# SmartVehicle_3.net
KiCad netlist of a schematic drawn in EAGLE
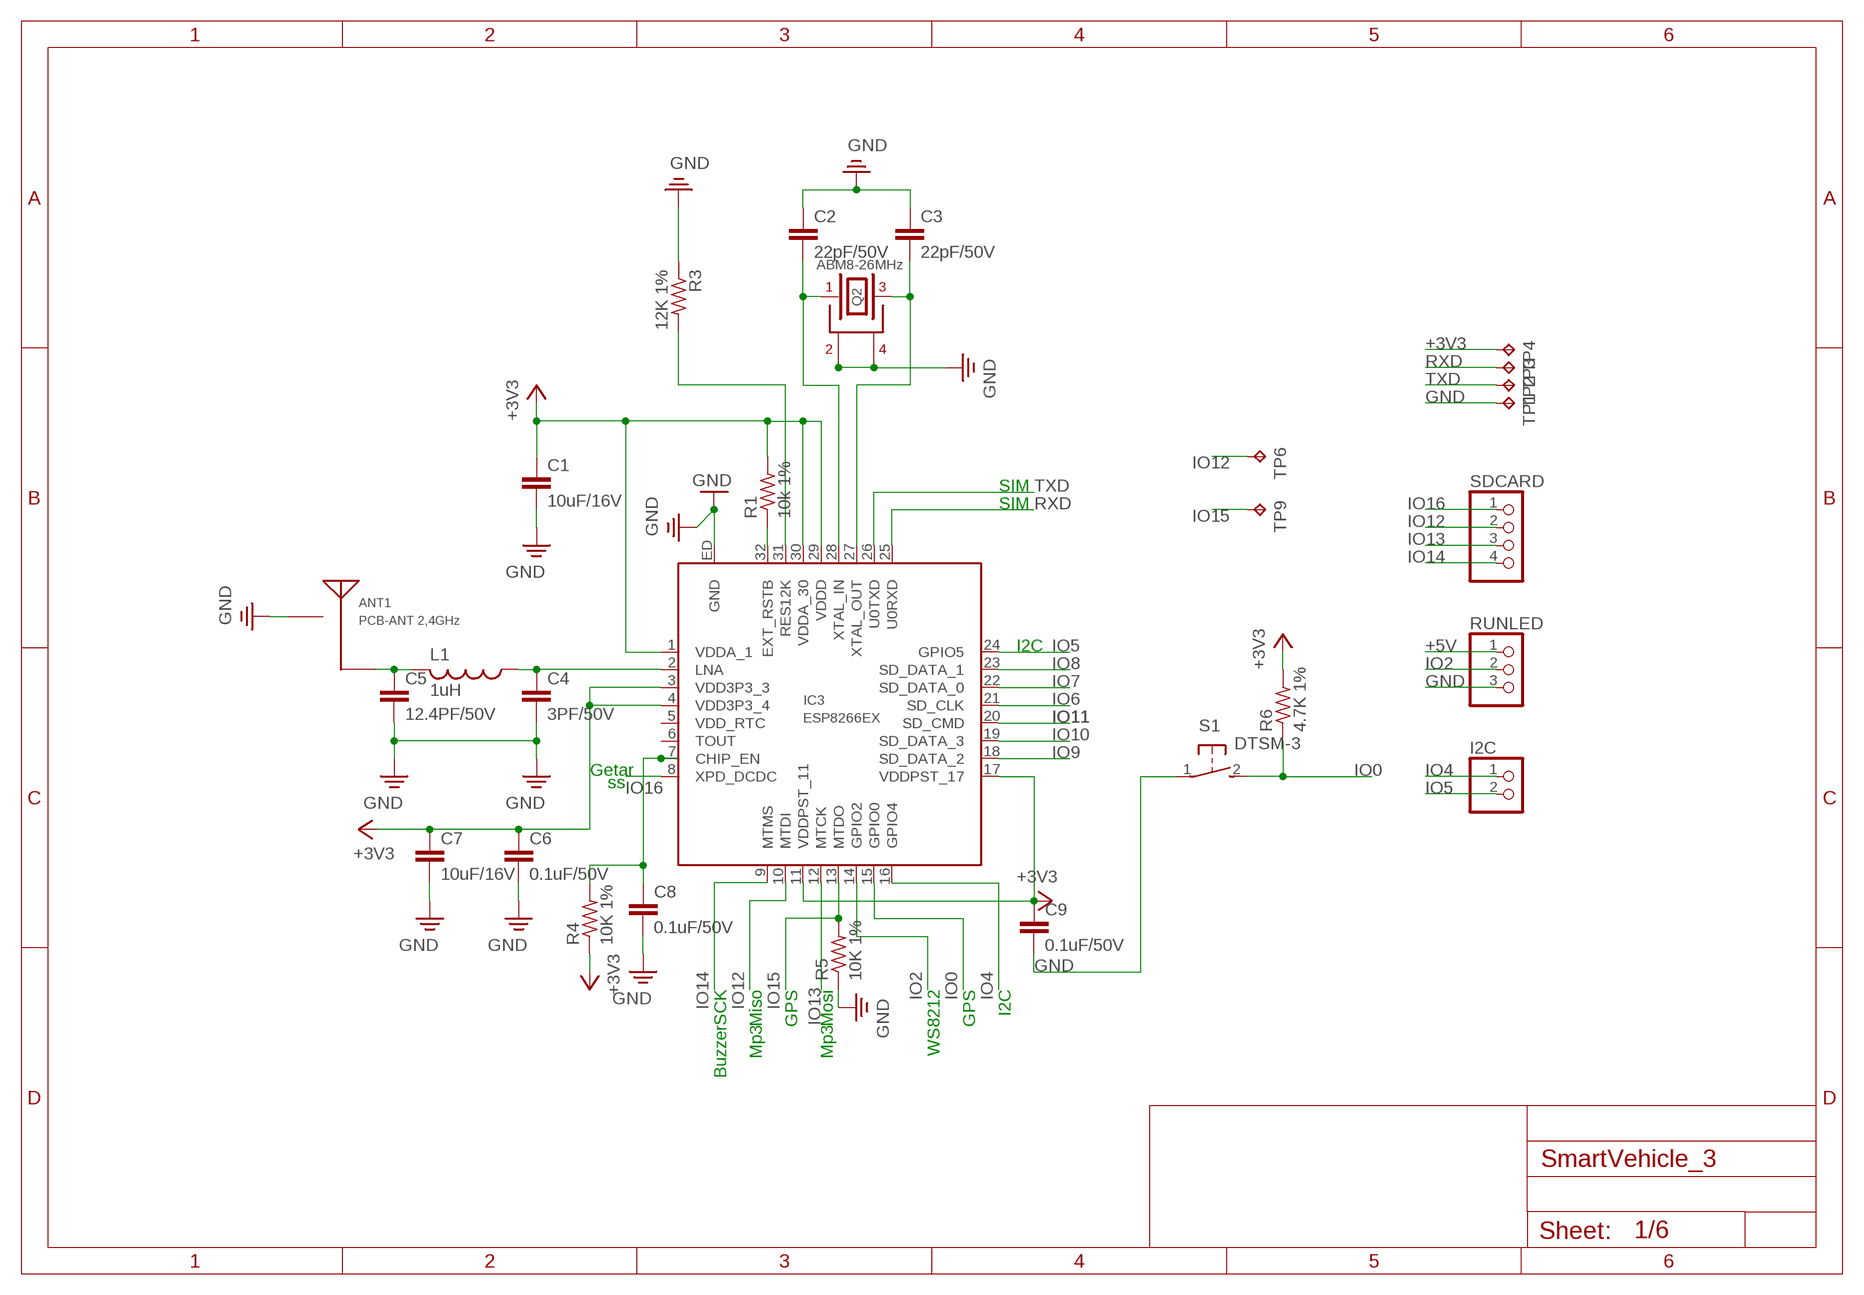
[diagram p0: schematic, sheet 1]
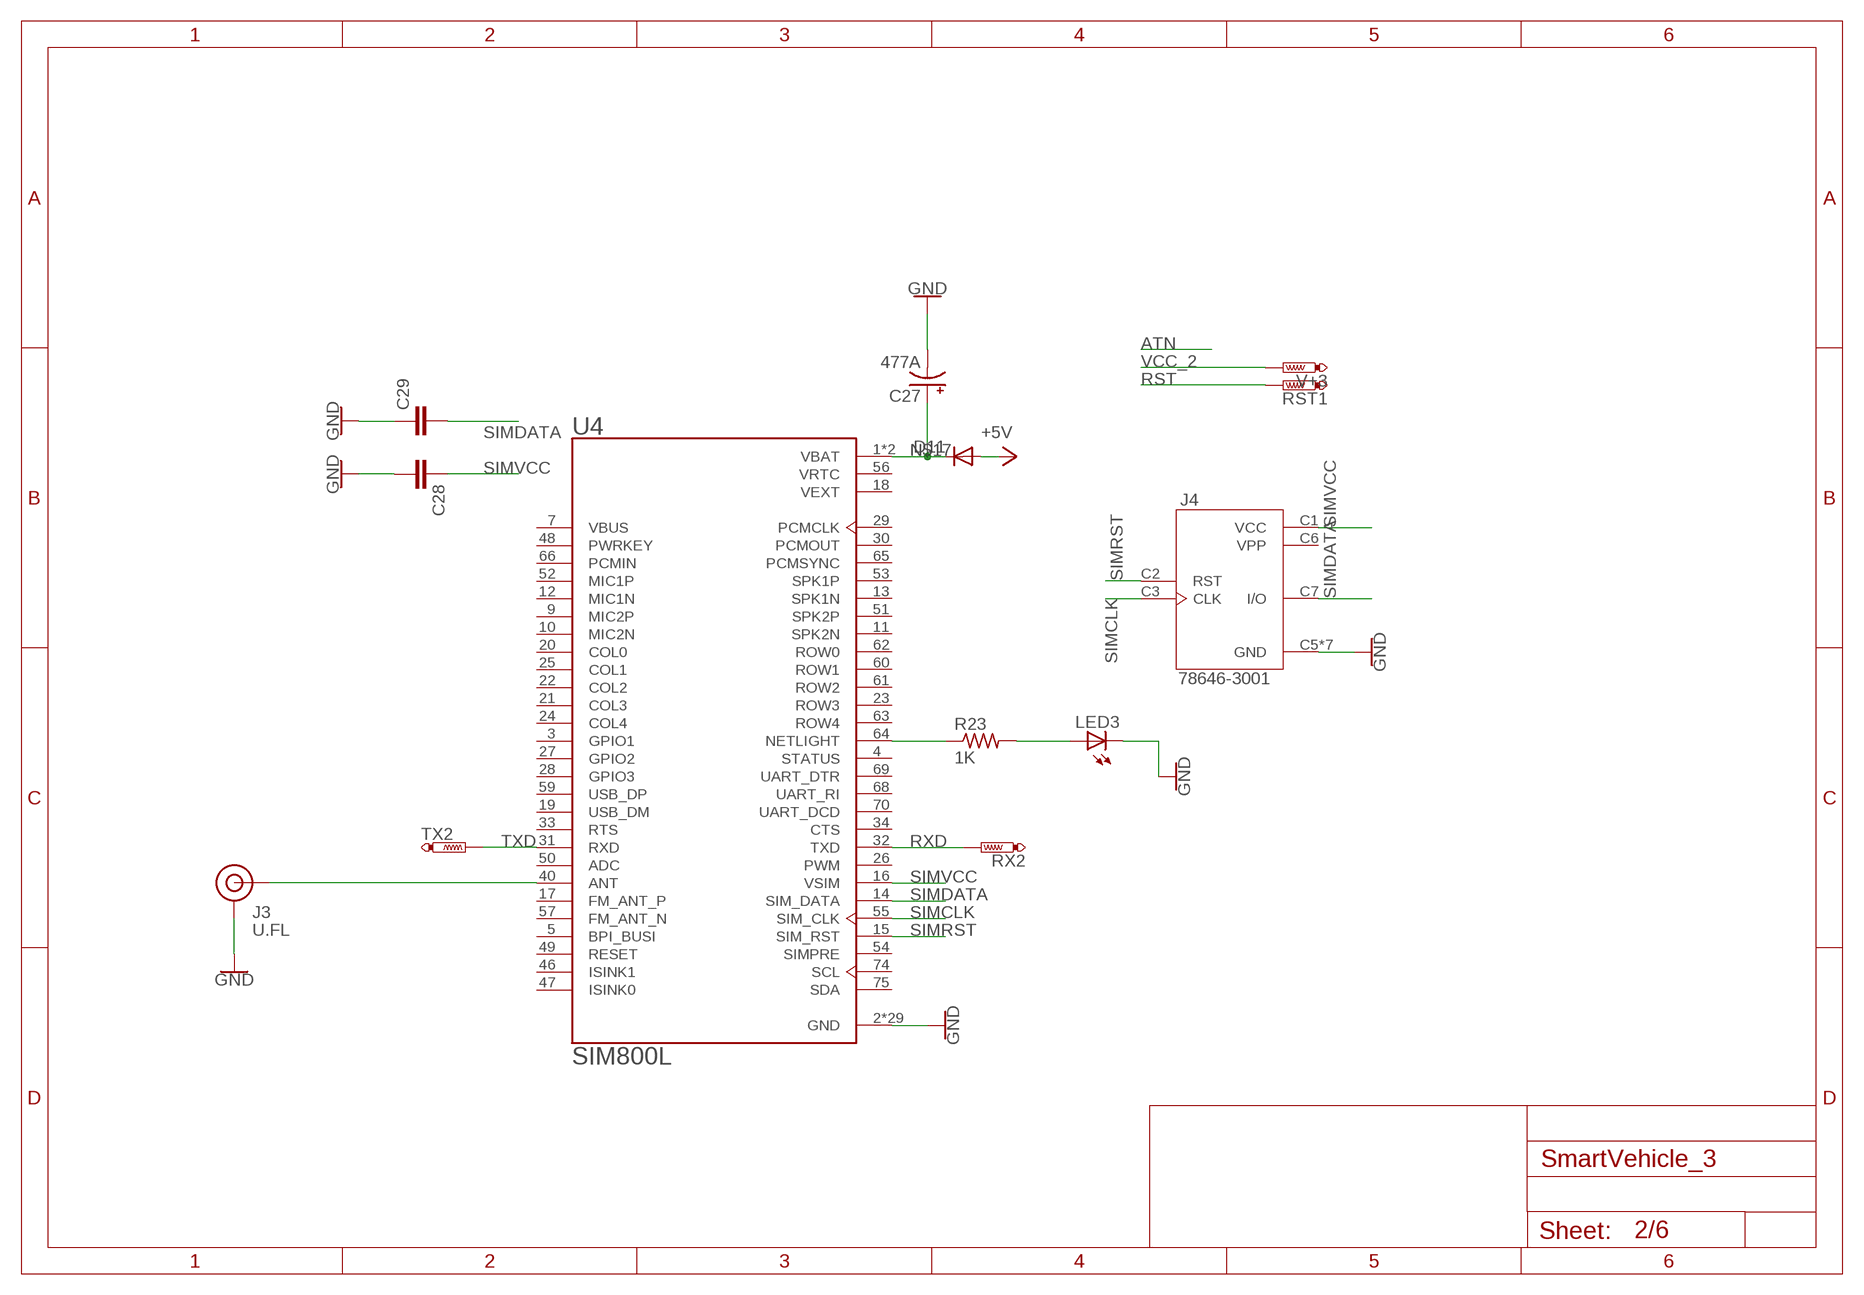
[diagram p1: schematic, sheet 2]
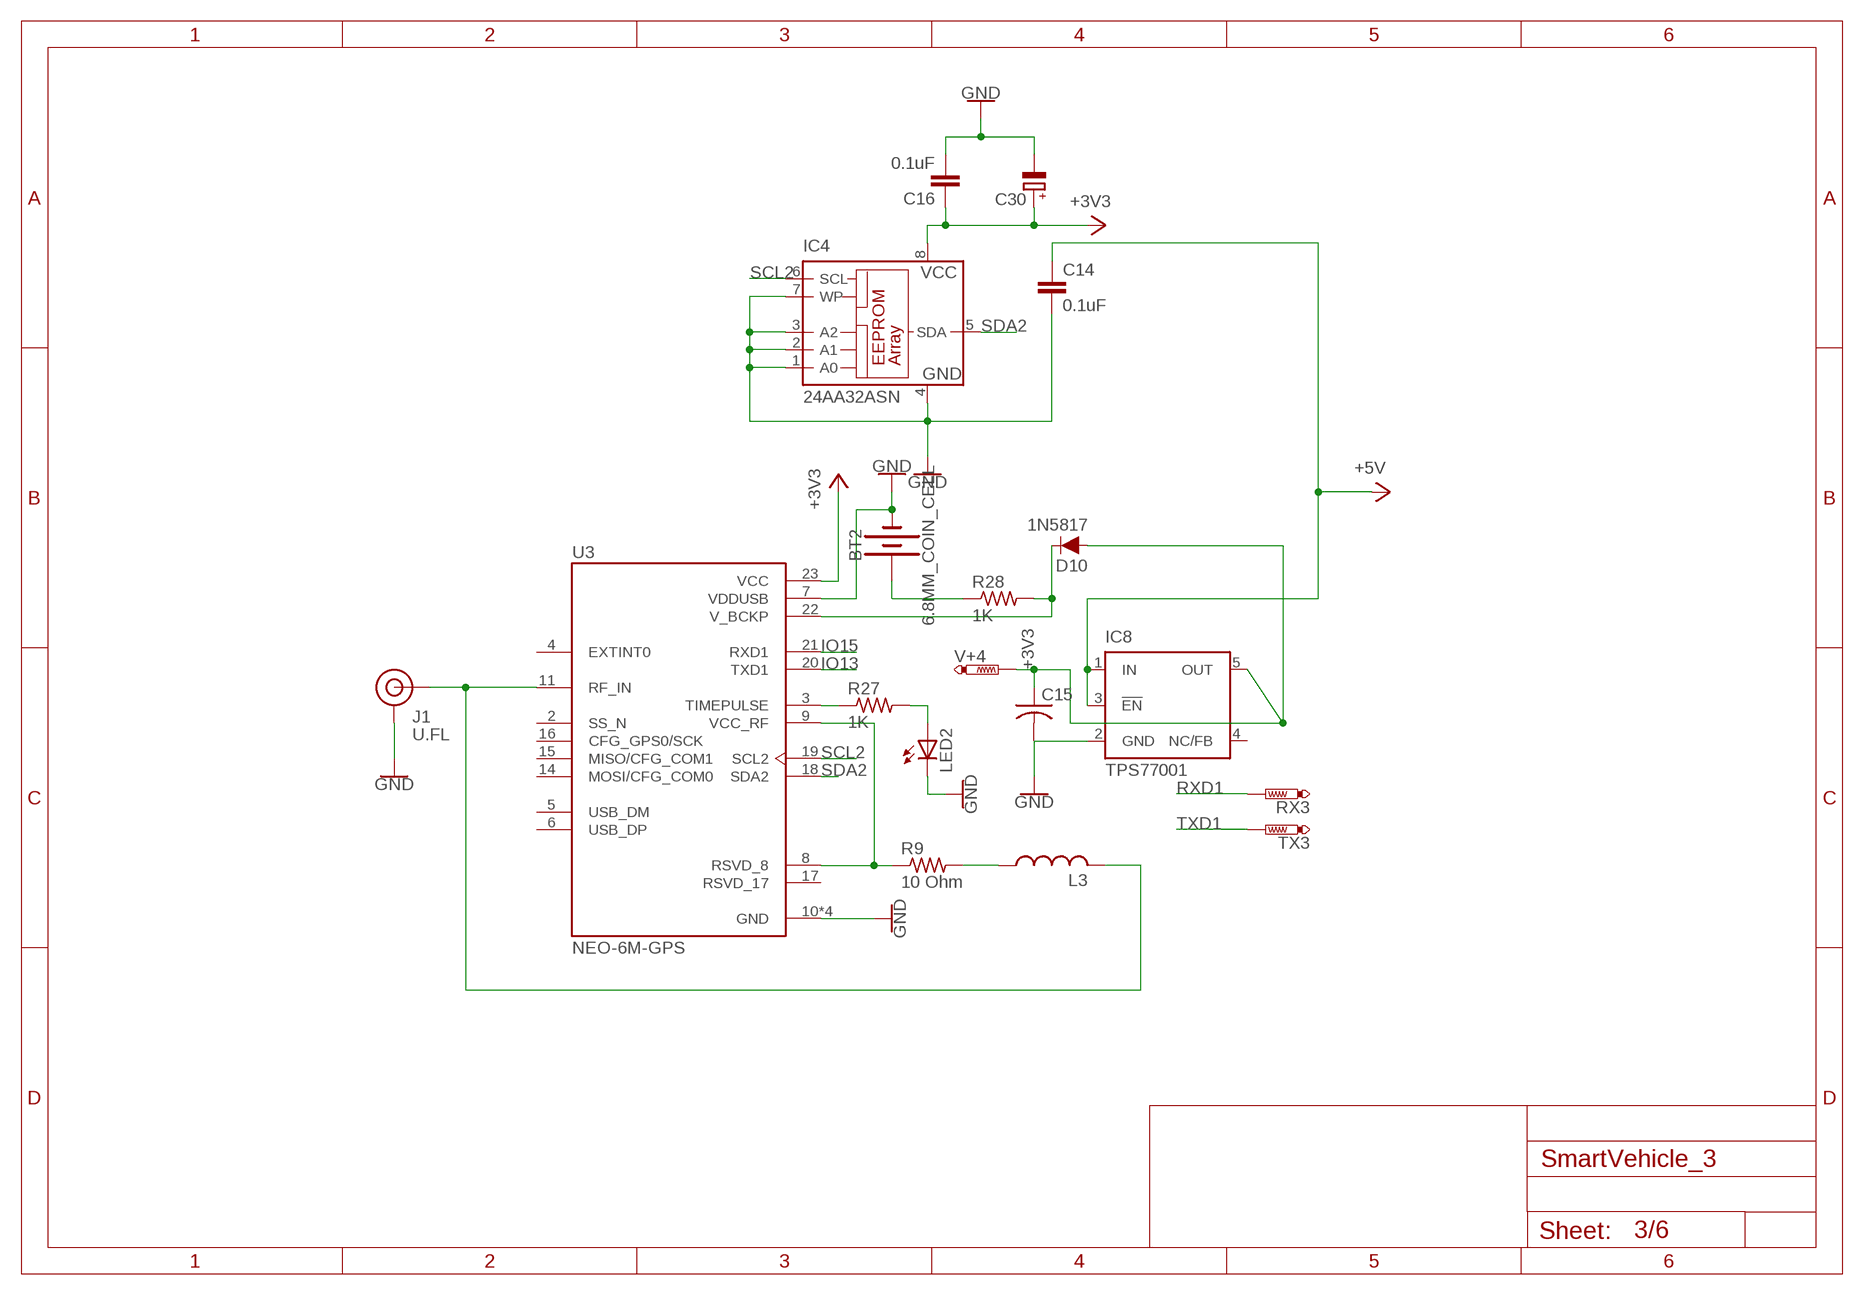
[diagram p2: schematic, sheet 3]
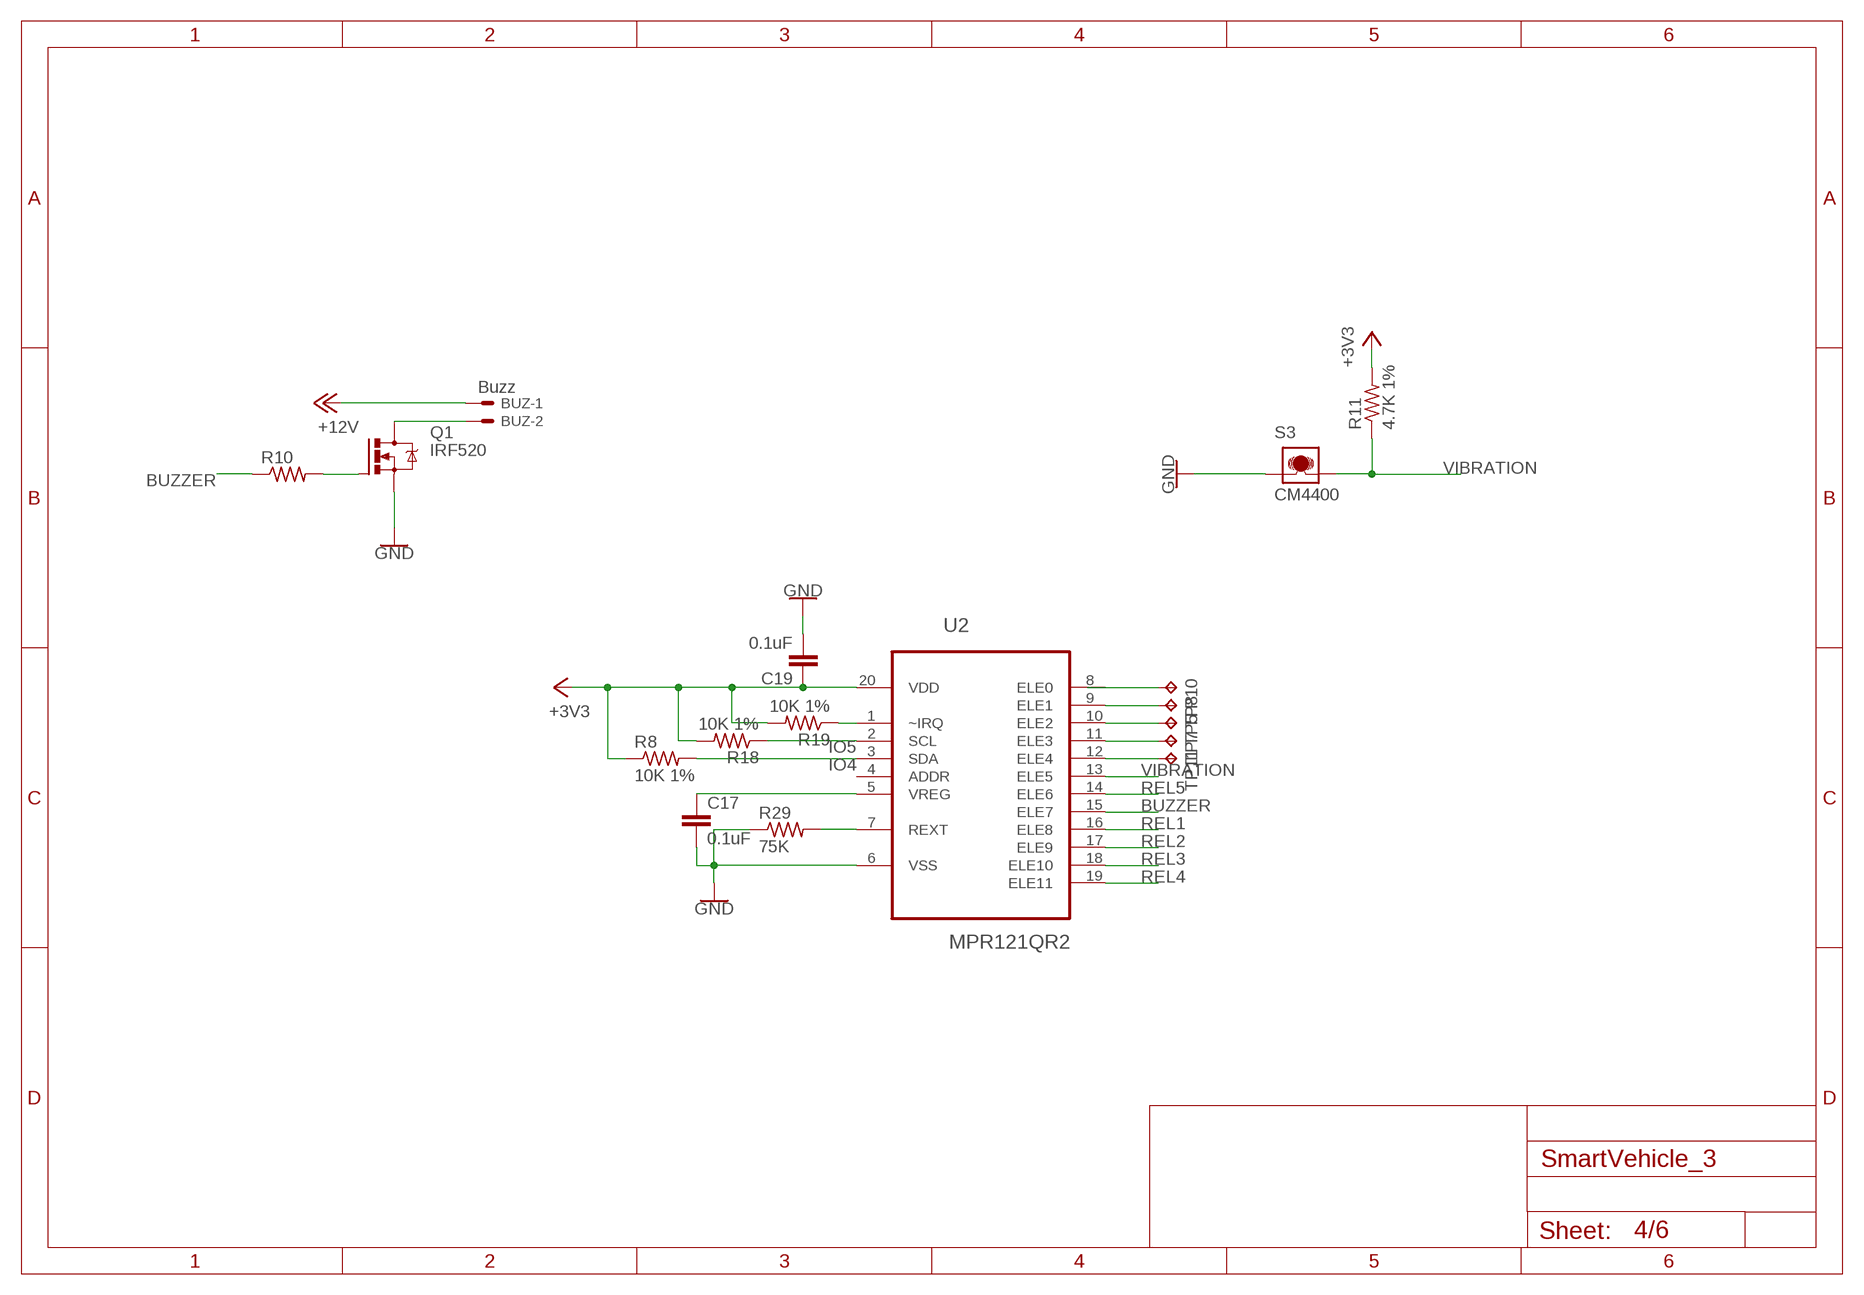
[diagram p3: schematic, sheet 4]
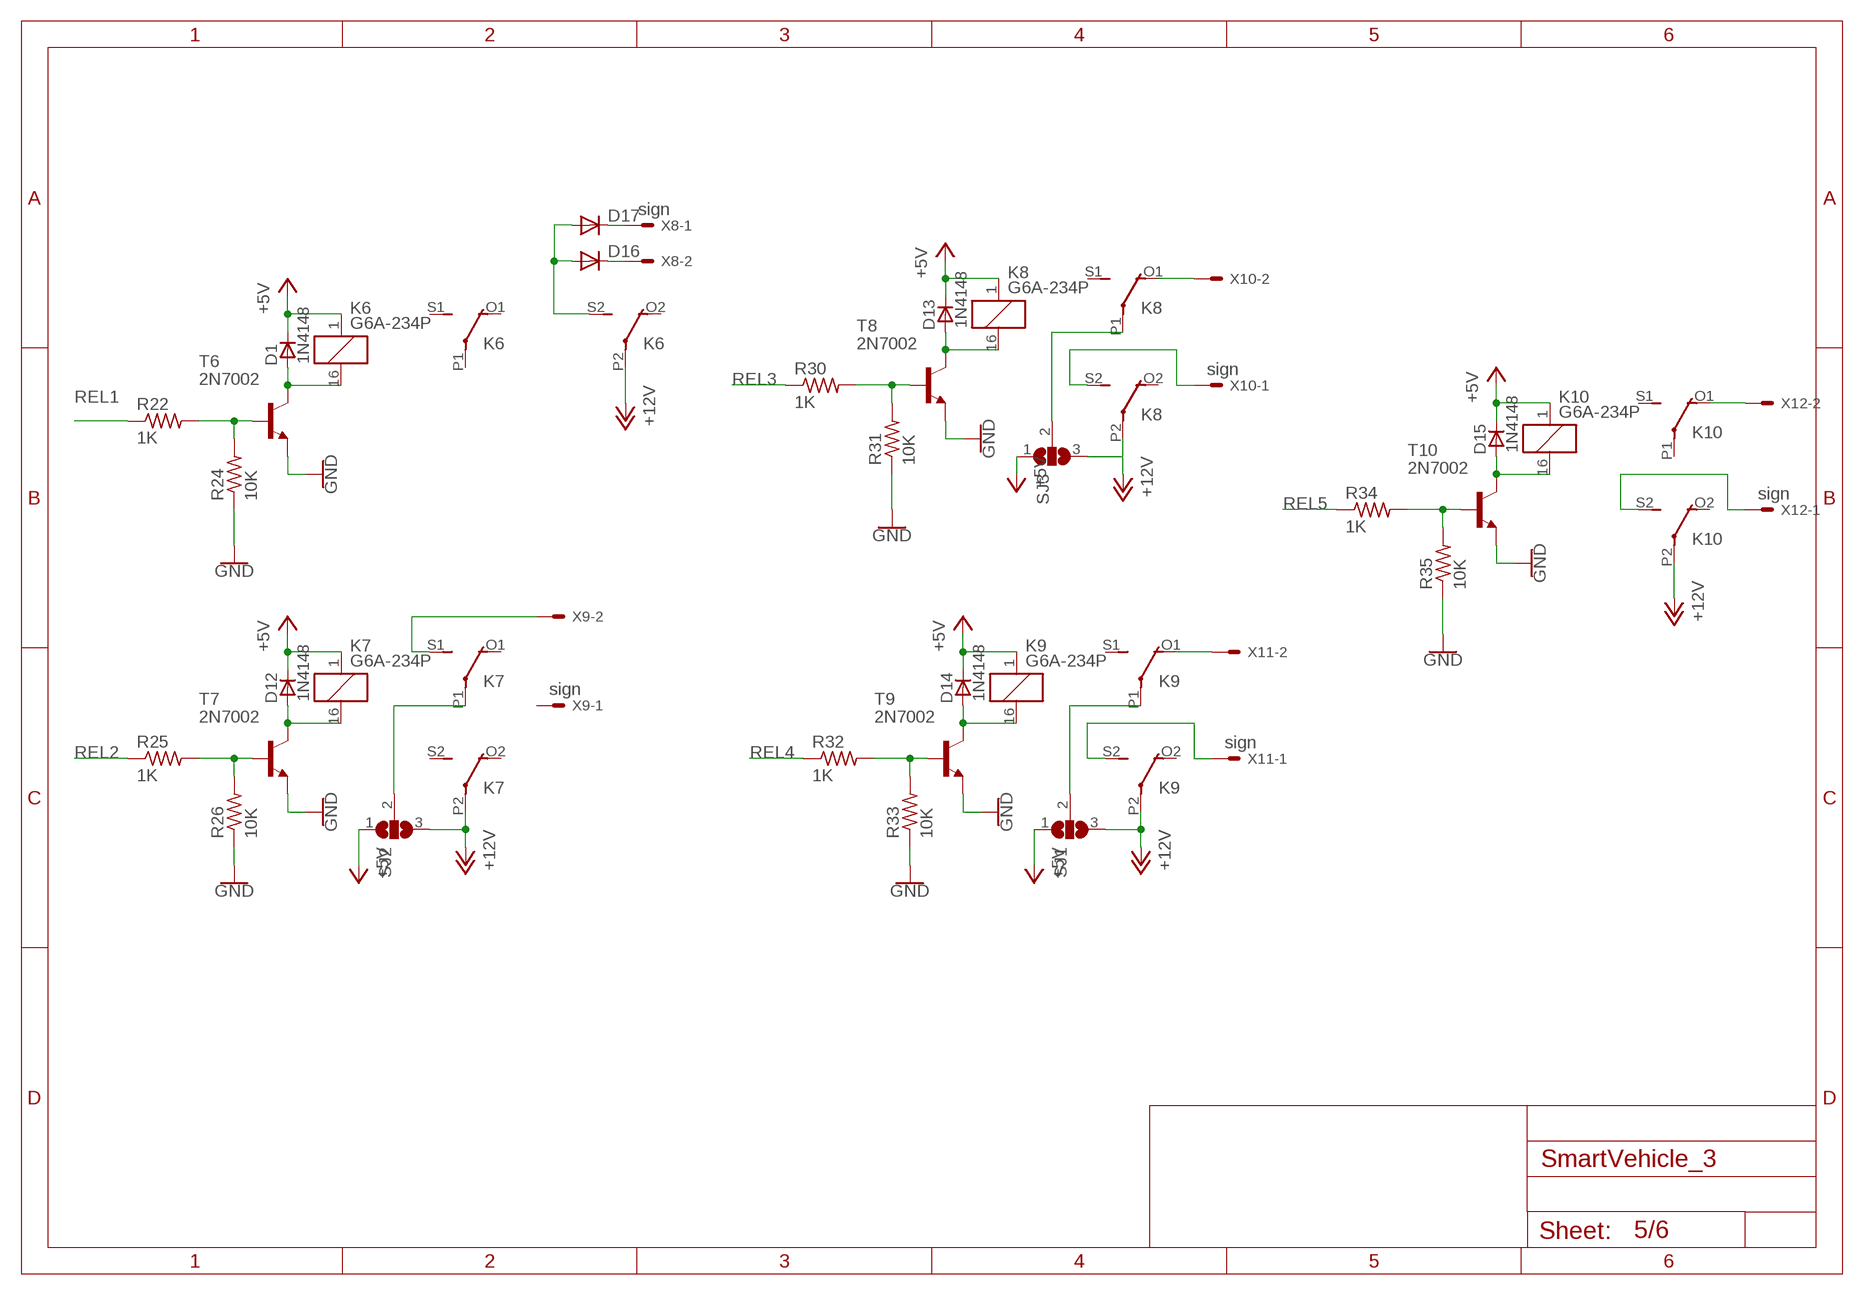
[diagram p4: schematic, sheet 5]
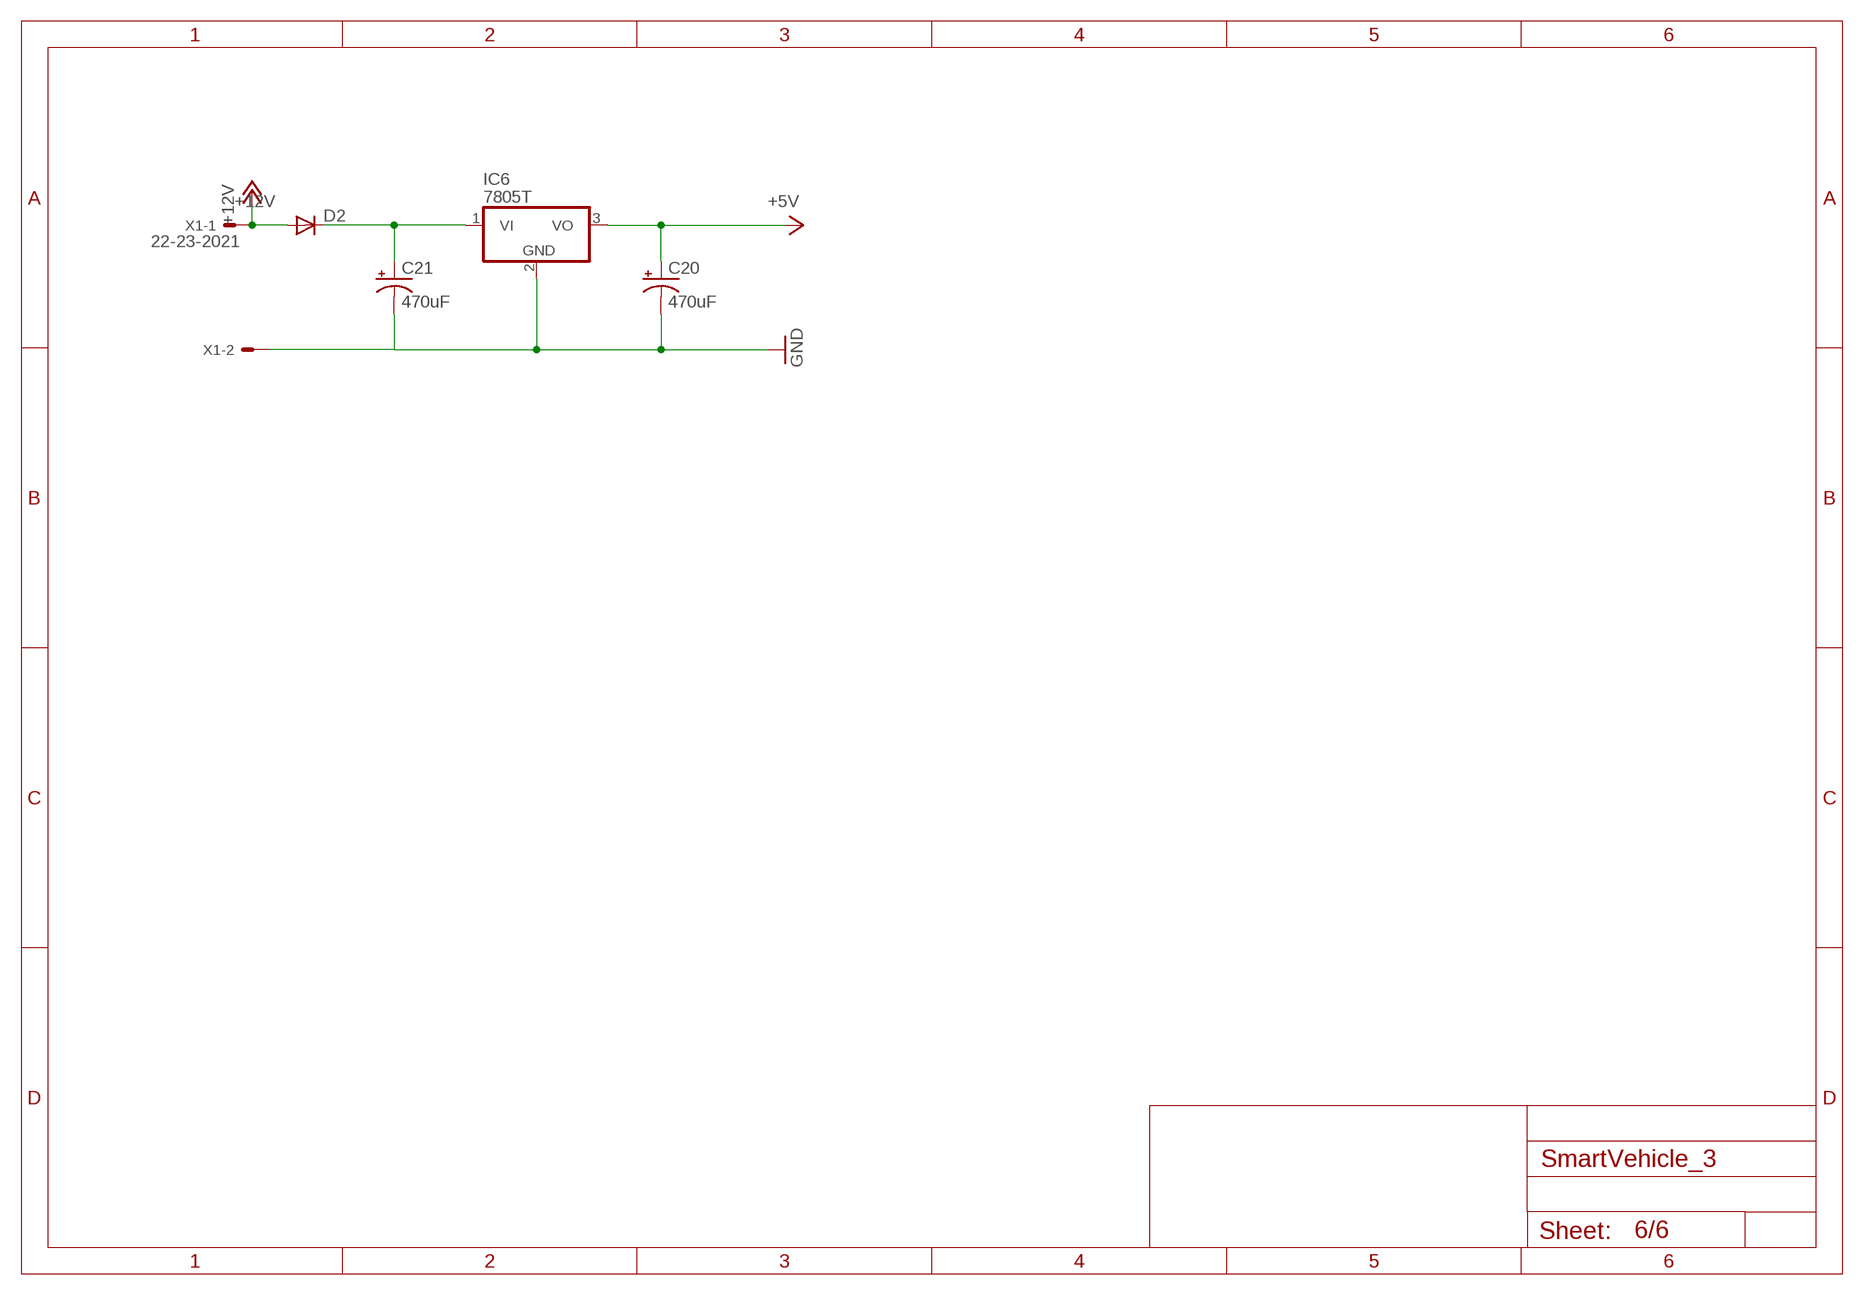
[diagram p5: schematic, sheet 6]

(export (version "E")
  (design (tool "Eeschema 10.0.6"))
  (components
    (comp (ref "BT2")
      (value "6.8MM_COIN_CELL")
      (footprint "eagle-import:BATTCON-6.8MM")
      (libsource (lib "eagle-import") (part "BATTERY-6.8MM_SMD"))
    )
    (comp (ref "C14")
      (value "0.1uF")
      (footprint "eagle-import:0603")
      (libsource (lib "eagle-import") (part "0.1UF-0603-25V-(+80/-20%)"))
    )
    (comp (ref "C15")
      (value "C-USC0603K")
      (footprint "eagle-import:C0603K")
      (libsource (lib "eagle-import") (part "C-USC0603K"))
    )
    (comp (ref "C16")
      (value "0.1uF")
      (footprint "eagle-import:0603")
      (libsource (lib "eagle-import") (part "0.1UF-0603-25V-(+80/-20%)"))
    )
    (comp (ref "C30")
      (value "CPOL-EUCT3528")
      (footprint "eagle-import:CT3528")
      (libsource (lib "eagle-import") (part "CPOL-EUCT3528"))
    )
    (comp (ref "D10")
      (value "1N5817")
      (footprint "eagle-import:SOD-323")
      (libsource (lib "eagle-import") (part "DIODE-BAS16J"))
    )
    (comp (ref "IC4")
      (value "24AA32ASN")
      (footprint "eagle-import:SO-08")
      (fields (field (name "MF") "MICROCHIP") (field (name "MPN") "24AA32A-I/SN"))
      (libsource (lib "eagle-import") (part "24SNAA32A"))
    )
    (comp (ref "IC8")
      (value "TPS77001")
      (footprint "eagle-import:SOT23-DBV")
      (fields (field (name "MF") "TEXAS INSTRUMENTS") (field (name "MPN") "TPS77001DBVT"))
      (libsource (lib "eagle-import") (part "TPS77001"))
    )
    (comp (ref "J1")
      (value "U.FL")
      (footprint "eagle-import:U.FL")
      (libsource (lib "eagle-import") (part "U.FL2PIN"))
    )
    (comp (ref "L3")
      (value "L-USL2012C")
      (footprint "eagle-import:L2012C")
      (libsource (lib "eagle-import") (part "L-USL2012C"))
    )
    (comp (ref "LED2")
      (value "LEDCHIP-LED0805")
      (footprint "eagle-import:CHIP-LED0805")
      (libsource (lib "eagle-import") (part "LEDCHIP-LED0805"))
    )
    (comp (ref "R9")
      (value "10 Ohm")
      (footprint "eagle-import:R0603")
      (libsource (lib "eagle-import") (part "R-US_R0603"))
    )
    (comp (ref "R27")
      (value "1K")
      (footprint "eagle-import:R0603")
      (libsource (lib "eagle-import") (part "R-US_R0603"))
    )
    (comp (ref "R28")
      (value "1K")
      (footprint "eagle-import:R0603")
      (libsource (lib "eagle-import") (part "R-US_R0603"))
    )
    (comp (ref "RX3")
      (value "PTR1TP08R")
      (footprint "eagle-import:TP08R")
      (libsource (lib "eagle-import") (part "PTR1TP08R"))
    )
    (comp (ref "TX3")
      (value "PTR1TP08R")
      (footprint "eagle-import:TP08R")
      (libsource (lib "eagle-import") (part "PTR1TP08R"))
    )
    (comp (ref "U3")
      (value "NEO-6M-GPS")
      (footprint "eagle-import:XCVR_NEO-6M-GPS")
      (fields (field (name "MF") "u-blox"))
      (libsource (lib "eagle-import") (part "NEO-6M-GPS"))
    )
    (comp (ref "V+4")
      (value "PTR1TP08R")
      (footprint "eagle-import:TP08R")
      (libsource (lib "eagle-import") (part "PTR1TP08R"))
    )
    (comp (ref "D1")
      (value "1N4148")
      (footprint "eagle-import:SOD80_DO213AA_MINIMELF")
      (libsource (lib "eagle-import") (part "LL4148"))
    )
    (comp (ref "D12")
      (value "1N4148")
      (footprint "eagle-import:SOD80_DO213AA_MINIMELF")
      (libsource (lib "eagle-import") (part "LL4148"))
    )
    (comp (ref "D13")
      (value "1N4148")
      (footprint "eagle-import:SOD80_DO213AA_MINIMELF")
      (libsource (lib "eagle-import") (part "LL4148"))
    )
    (comp (ref "D14")
      (value "1N4148")
      (footprint "eagle-import:SOD80_DO213AA_MINIMELF")
      (libsource (lib "eagle-import") (part "LL4148"))
    )
    (comp (ref "D15")
      (value "1N4148")
      (footprint "eagle-import:SOD80_DO213AA_MINIMELF")
      (libsource (lib "eagle-import") (part "LL4148"))
    )
    (comp (ref "D16")
      (value "DIODE-DO214AA")
      (footprint "eagle-import:DO214AA")
      (libsource (lib "eagle-import") (part "DIODE-DO214AA"))
    )
    (comp (ref "D17")
      (value "DIODE-DO214AA")
      (footprint "eagle-import:DO214AA")
      (libsource (lib "eagle-import") (part "DIODE-DO214AA"))
    )
    (comp (ref "K6")
      (value "G6A-234P")
      (footprint "eagle-import:G6A-234P")
      (libsource (lib "eagle-import") (part "G6A-234P"))
    )
    (comp (ref "K7")
      (value "G6A-234P")
      (footprint "eagle-import:G6A-234P")
      (libsource (lib "eagle-import") (part "G6A-234P"))
    )
    (comp (ref "K8")
      (value "G6A-234P")
      (footprint "eagle-import:G6A-234P")
      (libsource (lib "eagle-import") (part "G6A-234P"))
    )
    (comp (ref "K9")
      (value "G6A-234P")
      (footprint "eagle-import:G6A-234P")
      (libsource (lib "eagle-import") (part "G6A-234P"))
    )
    (comp (ref "K10")
      (value "G6A-234P")
      (footprint "eagle-import:G6A-234P")
      (libsource (lib "eagle-import") (part "G6A-234P"))
    )
    (comp (ref "R22")
      (value "1K")
      (footprint "eagle-import:M0805")
      (libsource (lib "eagle-import") (part "resistor_R-US_M0805"))
    )
    (comp (ref "R24")
      (value "10K")
      (footprint "eagle-import:M0805")
      (libsource (lib "eagle-import") (part "resistor_R-US_M0805"))
    )
    (comp (ref "R25")
      (value "1K")
      (footprint "eagle-import:M0805")
      (libsource (lib "eagle-import") (part "resistor_R-US_M0805"))
    )
    (comp (ref "R26")
      (value "10K")
      (footprint "eagle-import:M0805")
      (libsource (lib "eagle-import") (part "resistor_R-US_M0805"))
    )
    (comp (ref "R30")
      (value "1K")
      (footprint "eagle-import:M0805")
      (libsource (lib "eagle-import") (part "resistor_R-US_M0805"))
    )
    (comp (ref "R31")
      (value "10K")
      (footprint "eagle-import:M0805")
      (libsource (lib "eagle-import") (part "resistor_R-US_M0805"))
    )
    (comp (ref "R32")
      (value "1K")
      (footprint "eagle-import:M0805")
      (libsource (lib "eagle-import") (part "resistor_R-US_M0805"))
    )
    (comp (ref "R33")
      (value "10K")
      (footprint "eagle-import:M0805")
      (libsource (lib "eagle-import") (part "resistor_R-US_M0805"))
    )
    (comp (ref "R34")
      (value "1K")
      (footprint "eagle-import:M0805")
      (libsource (lib "eagle-import") (part "resistor_R-US_M0805"))
    )
    (comp (ref "R35")
      (value "10K")
      (footprint "eagle-import:M0805")
      (libsource (lib "eagle-import") (part "resistor_R-US_M0805"))
    )
    (comp (ref "SJ1")
      (value "SJ2W")
      (footprint "eagle-import:SJ_2")
      (libsource (lib "eagle-import") (part "SJ2W"))
    )
    (comp (ref "SJ2")
      (value "SJ2W")
      (footprint "eagle-import:SJ_2")
      (libsource (lib "eagle-import") (part "SJ2W"))
    )
    (comp (ref "SJ3")
      (value "SJ2W")
      (footprint "eagle-import:SJ_2")
      (libsource (lib "eagle-import") (part "SJ2W"))
    )
    (comp (ref "T6")
      (value "2N7002")
      (footprint "eagle-import:SOT23-BEC")
      (libsource (lib "eagle-import") (part "-NPN-SOT23-BECMMBT2222ALT1"))
    )
    (comp (ref "T7")
      (value "2N7002")
      (footprint "eagle-import:SOT23-BEC")
      (libsource (lib "eagle-import") (part "-NPN-SOT23-BECMMBT2222ALT1"))
    )
    (comp (ref "T8")
      (value "2N7002")
      (footprint "eagle-import:SOT23-BEC")
      (libsource (lib "eagle-import") (part "-NPN-SOT23-BECMMBT2222ALT1"))
    )
    (comp (ref "T9")
      (value "2N7002")
      (footprint "eagle-import:SOT23-BEC")
      (libsource (lib "eagle-import") (part "-NPN-SOT23-BECMMBT2222ALT1"))
    )
    (comp (ref "T10")
      (value "2N7002")
      (footprint "eagle-import:SOT23-BEC")
      (libsource (lib "eagle-import") (part "-NPN-SOT23-BECMMBT2222ALT1"))
    )
    (comp (ref "X8")
      (value "sign")
      (footprint "eagle-import:22-23-2021")
      (fields (field (name "MF") "MOLEX") (field (name "MPN") "22-23-2021"))
      (libsource (lib "eagle-import") (part "22-23-2021"))
    )
    (comp (ref "X9")
      (value "sign")
      (footprint "eagle-import:22-23-2021")
      (fields (field (name "MF") "MOLEX") (field (name "MPN") "22-23-2021"))
      (libsource (lib "eagle-import") (part "22-23-2021"))
    )
    (comp (ref "X10")
      (value "sign")
      (footprint "eagle-import:22-23-2021")
      (fields (field (name "MF") "MOLEX") (field (name "MPN") "22-23-2021"))
      (libsource (lib "eagle-import") (part "22-23-2021"))
    )
    (comp (ref "X11")
      (value "sign")
      (footprint "eagle-import:22-23-2021")
      (fields (field (name "MF") "MOLEX") (field (name "MPN") "22-23-2021"))
      (libsource (lib "eagle-import") (part "22-23-2021"))
    )
    (comp (ref "X12")
      (value "sign")
      (footprint "eagle-import:22-23-2021")
      (fields (field (name "MF") "MOLEX") (field (name "MPN") "22-23-2021"))
      (libsource (lib "eagle-import") (part "22-23-2021"))
    )
    (comp (ref "C20")
      (value "470uF")
      (footprint "eagle-import:E3,5-8")
      (libsource (lib "eagle-import") (part "CPOL-USE3.5-8"))
    )
    (comp (ref "C21")
      (value "470uF")
      (footprint "eagle-import:E3,5-8")
      (libsource (lib "eagle-import") (part "CPOL-USE3.5-8"))
    )
    (comp (ref "D2")
      (value "DIODE-DO214AC")
      (footprint "eagle-import:DO214AC")
      (libsource (lib "eagle-import") (part "DIODE-DO214AC"))
    )
    (comp (ref "IC6")
      (value "7805T")
      (footprint "eagle-import:TO220H")
      (libsource (lib "eagle-import") (part "78T05"))
    )
    (comp (ref "X1")
      (value "22-23-2021")
      (footprint "eagle-import:22-23-2021")
      (fields (field (name "MF") "MOLEX"))
      (libsource (lib "eagle-import") (part "22-23-2021"))
    )
    (comp (ref "BUZ")
      (value "Buzz")
      (footprint "eagle-import:22-23-2021")
      (fields (field (name "MF") "MOLEX") (field (name "MPN") "22-23-2021"))
      (libsource (lib "eagle-import") (part "22-23-2021"))
    )
    (comp (ref "C17")
      (value "0.1uF")
      (footprint "eagle-import:C0603")
      (libsource (lib "eagle-import") (part "C-EUC0603"))
    )
    (comp (ref "C19")
      (value "0.1uF")
      (footprint "eagle-import:C0603")
      (libsource (lib "eagle-import") (part "C-EUC0603"))
    )
    (comp (ref "Q1")
      (value "IRF520")
      (footprint "eagle-import:TO220BV")
      (libsource (lib "eagle-import") (part "IRF520"))
    )
    (comp (ref "R8")
      (value "10K 1%")
      (footprint "eagle-import:R0603")
      (libsource (lib "eagle-import") (part "resistor_R-US_R0603"))
    )
    (comp (ref "R10")
      (value "R-US_R0603")
      (footprint "eagle-import:R0603")
      (libsource (lib "eagle-import") (part "R-US_R0603"))
    )
    (comp (ref "R11")
      (value "4.7K 1%")
      (footprint "eagle-import:R0603")
      (libsource (lib "eagle-import") (part "resistor_R-US_R0603"))
    )
    (comp (ref "R18")
      (value "10K 1%")
      (footprint "eagle-import:R0603")
      (libsource (lib "eagle-import") (part "resistor_R-US_R0603"))
    )
    (comp (ref "R19")
      (value "10K 1%")
      (footprint "eagle-import:R0603")
      (libsource (lib "eagle-import") (part "resistor_R-US_R0603"))
    )
    (comp (ref "R29")
      (value "75K")
      (footprint "eagle-import:R0603")
      (libsource (lib "eagle-import") (part "resistor_R-US_R0603"))
    )
    (comp (ref "S3")
      (value "CM4400")
      (footprint "eagle-import:CM4400")
      (fields (field (name "MF") "FARNELL") (field (name "MPN") "CM4400-1."))
      (libsource (lib "eagle-import") (part "CM4400"))
    )
    (comp (ref "TP5")
      (value "TPB1,27")
      (footprint "eagle-import:B1,27")
      (libsource (lib "eagle-import") (part "TPB1,27"))
    )
    (comp (ref "TP7")
      (value "TPB1,27")
      (footprint "eagle-import:B1,27")
      (libsource (lib "eagle-import") (part "TPB1,27"))
    )
    (comp (ref "TP8")
      (value "TPB1,27")
      (footprint "eagle-import:B1,27")
      (libsource (lib "eagle-import") (part "TPB1,27"))
    )
    (comp (ref "TP10")
      (value "TPB1,27")
      (footprint "eagle-import:B1,27")
      (libsource (lib "eagle-import") (part "TPB1,27"))
    )
    (comp (ref "TP11")
      (value "TPB1,27")
      (footprint "eagle-import:B1,27")
      (libsource (lib "eagle-import") (part "TPB1,27"))
    )
    (comp (ref "U2")
      (value "MPR121QR2")
      (footprint "eagle-import:QFN40P300X300X60-20N")
      (fields (field (name "MF") "NXP USA"))
      (libsource (lib "eagle-import") (part "MPR121QR2"))
    )
    (comp (ref "C27")
      (value "477A")
      (footprint "eagle-import:CT7343")
      (libsource (lib "eagle-import") (part "CPOL-USCT7343"))
    )
    (comp (ref "C28")
      (value "C-EUC0805")
      (footprint "eagle-import:C0805")
      (libsource (lib "eagle-import") (part "C-EUC0805"))
    )
    (comp (ref "C29")
      (value "C-EUC0805")
      (footprint "eagle-import:C0805")
      (libsource (lib "eagle-import") (part "C-EUC0805"))
    )
    (comp (ref "D11")
      (value "DIODE-DO214AC")
      (footprint "eagle-import:DO214AC")
      (libsource (lib "eagle-import") (part "DIODE-DO214AC"))
    )
    (comp (ref "J3")
      (value "U.FL")
      (footprint "eagle-import:U.FL")
      (libsource (lib "eagle-import") (part "U.FL2PIN"))
    )
    (comp (ref "J4")
      (value "78646-3001")
      (footprint "eagle-import:MOLEX_78646-3001")
      (fields (field (name "MF") "Molex"))
      (libsource (lib "eagle-import") (part "78646-3001"))
    )
    (comp (ref "LED3")
      (value "LEDCHIP-LED0805")
      (footprint "eagle-import:CHIP-LED0805")
      (libsource (lib "eagle-import") (part "LEDCHIP-LED0805"))
    )
    (comp (ref "R23")
      (value "1K")
      (footprint "eagle-import:R0603")
      (libsource (lib "eagle-import") (part "R-US_R0603"))
    )
    (comp (ref "RST1")
      (value "PTR1TP08R")
      (footprint "eagle-import:TP08R")
      (libsource (lib "eagle-import") (part "PTR1TP08R"))
    )
    (comp (ref "RX2")
      (value "PTR1TP08R")
      (footprint "eagle-import:TP08R")
      (libsource (lib "eagle-import") (part "PTR1TP08R"))
    )
    (comp (ref "TX2")
      (value "PTR1TP08R")
      (footprint "eagle-import:TP08R")
      (libsource (lib "eagle-import") (part "PTR1TP08R"))
    )
    (comp (ref "U4")
      (value "SIM800L")
      (footprint "eagle-import:MODULE_SIM800L")
      (fields (field (name "MF") "Simcom"))
      (libsource (lib "eagle-import") (part "SIM800L"))
    )
    (comp (ref "V+3")
      (value "PTR1TP08R")
      (footprint "eagle-import:TP08R")
      (libsource (lib "eagle-import") (part "PTR1TP08R"))
    )
    (comp (ref "ANT1")
      (value "PCB-ANT 2,4GHz")
      (footprint "eagle-import:2.4GHZ_PCB")
      (libsource (lib "eagle-import") (part "2.4GHZ_PCB"))
    )
    (comp (ref "C1")
      (value "10uF/16V")
      (footprint "eagle-import:C0603")
      (libsource (lib "eagle-import") (part "C-EUC0603"))
    )
    (comp (ref "C2")
      (value "22pF/50V")
      (footprint "eagle-import:C0603")
      (libsource (lib "eagle-import") (part "C-EUC0603"))
    )
    (comp (ref "C3")
      (value "22pF/50V")
      (footprint "eagle-import:C0603")
      (libsource (lib "eagle-import") (part "C-EUC0603"))
    )
    (comp (ref "C4")
      (value "3PF/50V")
      (footprint "eagle-import:C0603")
      (libsource (lib "eagle-import") (part "C-EUC0603"))
    )
    (comp (ref "C5")
      (value "12.4PF/50V")
      (footprint "eagle-import:C0603")
      (libsource (lib "eagle-import") (part "C-EUC0603"))
    )
    (comp (ref "C6")
      (value "0.1uF/50V")
      (footprint "eagle-import:C0603")
      (libsource (lib "eagle-import") (part "C-EUC0603"))
    )
    (comp (ref "C7")
      (value "10uF/16V")
      (footprint "eagle-import:C0603")
      (libsource (lib "eagle-import") (part "C-EUC0603"))
    )
    (comp (ref "C8")
      (value "0.1uF/50V")
      (footprint "eagle-import:C0603")
      (libsource (lib "eagle-import") (part "C-EUC0603"))
    )
    (comp (ref "C9")
      (value "0.1uF/50V")
      (footprint "eagle-import:C0603")
      (libsource (lib "eagle-import") (part "C-EUC0603"))
    )
    (comp (ref "I2C")
      (value "PINHD-1X2")
      (footprint "eagle-import:1X02")
      (libsource (lib "eagle-import") (part "PINHD-1X2"))
    )
    (comp (ref "IC3")
      (value "ESP8266EX")
      (footprint "eagle-import:ESP8266EX")
      (libsource (lib "eagle-import") (part "ESP8266EX"))
    )
    (comp (ref "L1")
      (value "1uH")
      (footprint "eagle-import:L2012C")
      (libsource (lib "eagle-import") (part "resistor_L-USL2012C"))
    )
    (comp (ref "Q2")
      (value "ABM8-26MHz")
      (footprint "eagle-import:ABM8G")
      (libsource (lib "eagle-import") (part "ABM8G"))
    )
    (comp (ref "R1")
      (value "10k 1%")
      (footprint "eagle-import:R0603")
      (libsource (lib "eagle-import") (part "resistor_R-US_R0603"))
    )
    (comp (ref "R3")
      (value "12K 1%")
      (footprint "eagle-import:R0603")
      (libsource (lib "eagle-import") (part "resistor_R-US_R0603"))
    )
    (comp (ref "R4")
      (value "10K 1%")
      (footprint "eagle-import:R0603")
      (libsource (lib "eagle-import") (part "resistor_R-US_R0603"))
    )
    (comp (ref "R5")
      (value "10K 1%")
      (footprint "eagle-import:R0603")
      (libsource (lib "eagle-import") (part "resistor_R-US_R0603"))
    )
    (comp (ref "R6")
      (value "4.7K 1%")
      (footprint "eagle-import:R0603")
      (libsource (lib "eagle-import") (part "resistor_R-US_R0603"))
    )
    (comp (ref "RUNLED")
      (value "PINHD-1X3")
      (footprint "eagle-import:1X03")
      (libsource (lib "eagle-import") (part "PINHD-1X3"))
    )
    (comp (ref "S1")
      (value "DTSM-3")
      (footprint "eagle-import:DTSM-3")
      (libsource (lib "eagle-import") (part "DTSM-3"))
    )
    (comp (ref "SDCARD")
      (value "PINHD-1X4")
      (footprint "eagle-import:1X04")
      (libsource (lib "eagle-import") (part "PINHD-1X4"))
    )
    (comp (ref "TP1")
      (value "TPB1,27")
      (footprint "eagle-import:B1,27")
      (libsource (lib "eagle-import") (part "TPB1,27"))
    )
    (comp (ref "TP2")
      (value "TPB1,27")
      (footprint "eagle-import:B1,27")
      (libsource (lib "eagle-import") (part "TPB1,27"))
    )
    (comp (ref "TP3")
      (value "TPB1,27")
      (footprint "eagle-import:B1,27")
      (libsource (lib "eagle-import") (part "TPB1,27"))
    )
    (comp (ref "TP4")
      (value "TPB1,27")
      (footprint "eagle-import:B1,27")
      (libsource (lib "eagle-import") (part "TPB1,27"))
    )
    (comp (ref "TP6")
      (value "TPB1,27")
      (footprint "eagle-import:B1,27")
      (libsource (lib "eagle-import") (part "TPB1,27"))
    )
    (comp (ref "TP9")
      (value "TPB1,27")
      (footprint "eagle-import:B1,27")
      (libsource (lib "eagle-import") (part "TPB1,27"))
    )
  )
  (nets
    (net (code "1") (name "+3V3") (class "Default")
      (node (ref "C1") (pin "1") (pinfunction "1_1") (pintype "passive"))
      (node (ref "C15") (pin "1") (pinfunction "1_1") (pintype "passive"))
      (node (ref "C16") (pin "1") (pinfunction "1_1") (pintype "passive"))
      (node (ref "C19") (pin "1") (pinfunction "1_1") (pintype "passive"))
      (node (ref "C30") (pin "+") (pinfunction "+_+") (pintype "passive"))
      (node (ref "C6") (pin "1") (pinfunction "1_1") (pintype "passive"))
      (node (ref "C7") (pin "1") (pinfunction "1_1") (pintype "passive"))
      (node (ref "C9") (pin "1") (pinfunction "1_1") (pintype "passive"))
      (node (ref "D10") (pin "A") (pinfunction "A_A") (pintype "passive"))
      (node (ref "IC3") (pin "1") (pinfunction "VDDA_1_1") (pintype "bidirectional"))
      (node (ref "IC3") (pin "11") (pinfunction "VDDPST_11_11") (pintype "bidirectional"))
      (node (ref "IC3") (pin "17") (pinfunction "VDDPST_17_17") (pintype "bidirectional"))
      (node (ref "IC3") (pin "29") (pinfunction "VDDD_29") (pintype "bidirectional"))
      (node (ref "IC3") (pin "3") (pinfunction "VDD3P3_3_3") (pintype "bidirectional"))
      (node (ref "IC3") (pin "30") (pinfunction "VDDA_30_30") (pintype "bidirectional"))
      (node (ref "IC3") (pin "4") (pinfunction "VDD3P3_4_4") (pintype "bidirectional"))
      (node (ref "IC4") (pin "8") (pinfunction "VCC_8") (pintype "power_in"))
      (node (ref "IC8") (pin "5") (pinfunction "OUT_5") (pintype "passive"))
      (node (ref "R1") (pin "2") (pinfunction "2_2") (pintype "passive"))
      (node (ref "R11") (pin "2") (pinfunction "2_2") (pintype "passive"))
      (node (ref "R18") (pin "2") (pinfunction "2_2") (pintype "passive"))
      (node (ref "R19") (pin "2") (pinfunction "2_2") (pintype "passive"))
      (node (ref "R4") (pin "1") (pinfunction "1_1") (pintype "passive"))
      (node (ref "R6") (pin "2") (pinfunction "2_2") (pintype "passive"))
      (node (ref "R8") (pin "1") (pinfunction "1_1") (pintype "passive"))
      (node (ref "TP4") (pin "TP") (pinfunction "TP_TP") (pintype "input"))
      (node (ref "U2") (pin "20") (pinfunction "VDD_20") (pintype "power_in"))
      (node (ref "U3") (pin "23") (pinfunction "VCC_23") (pintype "power_in"))
      (node (ref "V+4") (pin "TP") (pinfunction "TP_TP") (pintype "input"))
    )
    (net (code "2") (name "+5V") (class "Default")
      (node (ref "C14") (pin "1") (pinfunction "1_1") (pintype "passive"))
      (node (ref "C20") (pin "+") (pinfunction "+_+") (pintype "passive"))
      (node (ref "D1") (pin "C") (pinfunction "C_C") (pintype "passive"))
      (node (ref "D11") (pin "A") (pinfunction "A_A") (pintype "passive"))
      (node (ref "D12") (pin "C") (pinfunction "C_C") (pintype "passive"))
      (node (ref "D13") (pin "C") (pinfunction "C_C") (pintype "passive"))
      (node (ref "D14") (pin "C") (pinfunction "C_C") (pintype "passive"))
      (node (ref "D15") (pin "C") (pinfunction "C_C") (pintype "passive"))
      (node (ref "IC6") (pin "3") (pinfunction "VO_3") (pintype "passive"))
      (node (ref "IC8") (pin "1") (pinfunction "IN_1") (pintype "input"))
      (node (ref "IC8") (pin "3") (pinfunction "~{EN}_3") (pintype "input"))
      (node (ref "K10") (pin "1") (pinfunction "1_1") (pintype "passive"))
      (node (ref "K6") (pin "1") (pinfunction "1_1") (pintype "passive"))
      (node (ref "K7") (pin "1") (pinfunction "1_1") (pintype "passive"))
      (node (ref "K8") (pin "1") (pinfunction "1_1") (pintype "passive"))
      (node (ref "K9") (pin "1") (pinfunction "1_1") (pintype "passive"))
      (node (ref "RUNLED") (pin "1") (pinfunction "1_1") (pintype "passive"))
      (node (ref "SJ1") (pin "1") (pinfunction "1_1") (pintype "passive"))
      (node (ref "SJ2") (pin "1") (pinfunction "1_1") (pintype "passive"))
      (node (ref "SJ3") (pin "1") (pinfunction "1_1") (pintype "passive"))
    )
    (net (code "3") (name "+12V") (class "Default")
      (node (ref "BUZ") (pin "1") (pinfunction "S_1") (pintype "passive"))
      (node (ref "D2") (pin "A") (pinfunction "A_A") (pintype "passive"))
      (node (ref "K10") (pin "P2") (pinfunction "P_P2") (pintype "passive"))
      (node (ref "K6") (pin "P2") (pinfunction "P_P2") (pintype "passive"))
      (node (ref "K7") (pin "P2") (pinfunction "P_P2") (pintype "passive"))
      (node (ref "K8") (pin "P2") (pinfunction "P_P2") (pintype "passive"))
      (node (ref "K9") (pin "P2") (pinfunction "P_P2") (pintype "passive"))
      (node (ref "SJ1") (pin "3") (pinfunction "3_3") (pintype "passive"))
      (node (ref "SJ2") (pin "3") (pinfunction "3_3") (pintype "passive"))
      (node (ref "SJ3") (pin "3") (pinfunction "3_3") (pintype "passive"))
      (node (ref "X1") (pin "1") (pinfunction "S_1") (pintype "passive"))
    )
    (net (code "5") (name "BUZZER") (class "Default")
      (node (ref "R10") (pin "1") (pinfunction "1_1") (pintype "passive"))
      (node (ref "U2") (pin "15") (pinfunction "ELE7_15") (pintype "output"))
    )
    (net (code "6") (name "GND") (class "Default")
      (node (ref "ANT1") (pin "GND") (pinfunction "2_GND") (pintype "bidirectional"))
      (node (ref "BT2") (pin "-") (pinfunction "-_-") (pintype "power_in"))
      (node (ref "C1") (pin "2") (pinfunction "2_2") (pintype "passive"))
      (node (ref "C14") (pin "2") (pinfunction "2_2") (pintype "passive"))
      (node (ref "C15") (pin "2") (pinfunction "2_2") (pintype "passive"))
      (node (ref "C16") (pin "2") (pinfunction "2_2") (pintype "passive"))
      (node (ref "C17") (pin "2") (pinfunction "2_2") (pintype "passive"))
      (node (ref "C19") (pin "2") (pinfunction "2_2") (pintype "passive"))
      (node (ref "C2") (pin "1") (pinfunction "1_1") (pintype "passive"))
      (node (ref "C20") (pin "-") (pinfunction "-_-") (pintype "passive"))
      (node (ref "C21") (pin "-") (pinfunction "-_-") (pintype "passive"))
      (node (ref "C27") (pin "-") (pinfunction "-_-") (pintype "passive"))
      (node (ref "C28") (pin "2") (pinfunction "2_2") (pintype "passive"))
      (node (ref "C29") (pin "1") (pinfunction "1_1") (pintype "passive"))
      (node (ref "C3") (pin "1") (pinfunction "1_1") (pintype "passive"))
      (node (ref "C30") (pin "-") (pinfunction "-_-") (pintype "passive"))
      (node (ref "C4") (pin "2") (pinfunction "2_2") (pintype "passive"))
      (node (ref "C5") (pin "2") (pinfunction "2_2") (pintype "passive"))
      (node (ref "C6") (pin "2") (pinfunction "2_2") (pintype "passive"))
      (node (ref "C7") (pin "2") (pinfunction "2_2") (pintype "passive"))
      (node (ref "C8") (pin "2") (pinfunction "2_2") (pintype "passive"))
      (node (ref "C9") (pin "2") (pinfunction "2_2") (pintype "passive"))
      (node (ref "IC3") (pin "ED") (pinfunction "GND_ED") (pintype "bidirectional"))
      (node (ref "IC4") (pin "1") (pinfunction "A0_1") (pintype "input"))
      (node (ref "IC4") (pin "2") (pinfunction "A1_2") (pintype "input"))
      (node (ref "IC4") (pin "3") (pinfunction "A2_3") (pintype "input"))
      (node (ref "IC4") (pin "4") (pinfunction "GND_4") (pintype "power_in"))
      (node (ref "IC4") (pin "7") (pinfunction "WP_7") (pintype "input"))
      (node (ref "IC6") (pin "2") (pinfunction "GND_2") (pintype "passive"))
      (node (ref "IC8") (pin "2") (pinfunction "GND_2") (pintype "power_in"))
      (node (ref "J1") (pin "1") (pinfunction "GND_1") (pintype "bidirectional"))
      (node (ref "J1") (pin "2") (pinfunction "GND_2") (pintype "bidirectional"))
      (node (ref "J3") (pin "1") (pinfunction "GND_1") (pintype "bidirectional"))
      (node (ref "J3") (pin "2") (pinfunction "GND_2") (pintype "bidirectional"))
      (node (ref "J4") (pin "C5") (pinfunction "GND_C5") (pintype "power_in"))
      (node (ref "J4") (pin "G1") (pinfunction "GND_G1") (pintype "power_in"))
      (node (ref "J4") (pin "G2") (pinfunction "GND_G2") (pintype "power_in"))
      (node (ref "J4") (pin "G3") (pinfunction "GND_G3") (pintype "power_in"))
      (node (ref "J4") (pin "G4") (pinfunction "GND_G4") (pintype "power_in"))
      (node (ref "J4") (pin "G5") (pinfunction "GND_G5") (pintype "power_in"))
      (node (ref "J4") (pin "G6") (pinfunction "GND_G6") (pintype "power_in"))
      (node (ref "LED2") (pin "C") (pinfunction "C_C") (pintype "passive"))
      (node (ref "LED3") (pin "C") (pinfunction "C_C") (pintype "passive"))
      (node (ref "Q1") (pin "S") (pinfunction "S_S") (pintype "passive"))
      (node (ref "Q2") (pin "2") (pinfunction "2_2") (pintype "bidirectional"))
      (node (ref "Q2") (pin "4") (pinfunction "4_4") (pintype "bidirectional"))
      (node (ref "R24") (pin "1") (pinfunction "1_1") (pintype "passive"))
      (node (ref "R26") (pin "1") (pinfunction "1_1") (pintype "passive"))
      (node (ref "R29") (pin "1") (pinfunction "1_1") (pintype "passive"))
      (node (ref "R3") (pin "1") (pinfunction "1_1") (pintype "passive"))
      (node (ref "R31") (pin "1") (pinfunction "1_1") (pintype "passive"))
      (node (ref "R33") (pin "1") (pinfunction "1_1") (pintype "passive"))
      (node (ref "R35") (pin "1") (pinfunction "1_1") (pintype "passive"))
      (node (ref "R5") (pin "1") (pinfunction "1_1") (pintype "passive"))
      (node (ref "RUNLED") (pin "3") (pinfunction "3_3") (pintype "passive"))
      (node (ref "S1") (pin "1") (pinfunction "1_1") (pintype "passive"))
      (node (ref "S3") (pin "1") (pinfunction "1_1") (pintype "passive"))
      (node (ref "T10") (pin "E") (pinfunction "E_E") (pintype "passive"))
      (node (ref "T6") (pin "E") (pinfunction "E_E") (pintype "passive"))
      (node (ref "T7") (pin "E") (pinfunction "E_E") (pintype "passive"))
      (node (ref "T8") (pin "E") (pinfunction "E_E") (pintype "passive"))
      (node (ref "T9") (pin "E") (pinfunction "E_E") (pintype "passive"))
      (node (ref "TP1") (pin "TP") (pinfunction "TP_TP") (pintype "input"))
      (node (ref "U2") (pin "6") (pinfunction "VSS_6") (pintype "power_in"))
      (node (ref "U3") (pin "10") (pinfunction "GND_10") (pintype "power_in"))
      (node (ref "U3") (pin "12") (pinfunction "GND_12") (pintype "power_in"))
      (node (ref "U3") (pin "13") (pinfunction "GND_13") (pintype "power_in"))
      (node (ref "U3") (pin "24") (pinfunction "GND_24") (pintype "power_in"))
      (node (ref "U3") (pin "7") (pinfunction "VDDUSB_7") (pintype "power_in"))
      (node (ref "U4") (pin "2") (pinfunction "GND_2") (pintype "power_in"))
      (node (ref "U4") (pin "35") (pinfunction "GND_35") (pintype "power_in"))
      (node (ref "U4") (pin "37") (pinfunction "GND_37") (pintype "power_in"))
      (node (ref "U4") (pin "38") (pinfunction "GND_38") (pintype "power_in"))
      (node (ref "U4") (pin "39") (pinfunction "GND_39") (pintype "power_in"))
      (node (ref "U4") (pin "41") (pinfunction "GND_41") (pintype "power_in"))
      (node (ref "U4") (pin "43") (pinfunction "GND_43") (pintype "power_in"))
      (node (ref "U4") (pin "44") (pinfunction "GND_44") (pintype "power_in"))
      (node (ref "U4") (pin "45") (pinfunction "GND_45") (pintype "power_in"))
      (node (ref "U4") (pin "58") (pinfunction "GND_58") (pintype "power_in"))
      (node (ref "U4") (pin "6") (pinfunction "GND_6") (pintype "power_in"))
      (node (ref "U4") (pin "67") (pinfunction "GND_67") (pintype "power_in"))
      (node (ref "U4") (pin "71") (pinfunction "GND_71") (pintype "power_in"))
      (node (ref "U4") (pin "72") (pinfunction "GND_72") (pintype "power_in"))
      (node (ref "U4") (pin "73") (pinfunction "GND_73") (pintype "power_in"))
      (node (ref "U4") (pin "76") (pinfunction "GND_76") (pintype "power_in"))
      (node (ref "U4") (pin "77") (pinfunction "GND_77") (pintype "power_in"))
      (node (ref "U4") (pin "78") (pinfunction "GND_78") (pintype "power_in"))
      (node (ref "U4") (pin "79") (pinfunction "GND_79") (pintype "power_in"))
      (node (ref "U4") (pin "8") (pinfunction "GND_8") (pintype "power_in"))
      (node (ref "U4") (pin "80") (pinfunction "GND_80") (pintype "power_in"))
      (node (ref "U4") (pin "81") (pinfunction "GND_81") (pintype "power_in"))
      (node (ref "U4") (pin "82") (pinfunction "GND_82") (pintype "power_in"))
      (node (ref "U4") (pin "83") (pinfunction "GND_83") (pintype "power_in"))
      (node (ref "U4") (pin "84") (pinfunction "GND_84") (pintype "power_in"))
      (node (ref "U4") (pin "85") (pinfunction "GND_85") (pintype "power_in"))
      (node (ref "U4") (pin "86") (pinfunction "GND_86") (pintype "power_in"))
      (node (ref "U4") (pin "87") (pinfunction "GND_87") (pintype "power_in"))
      (node (ref "U4") (pin "88") (pinfunction "GND_88") (pintype "power_in"))
      (node (ref "X1") (pin "2") (pinfunction "S_2") (pintype "passive"))
    )
    (net (code "7") (name "IO0") (class "Default")
      (node (ref "IC3") (pin "15") (pinfunction "GPIO0_15") (pintype "bidirectional"))
      (node (ref "R6") (pin "1") (pinfunction "1_1") (pintype "passive"))
      (node (ref "S1") (pin "2") (pinfunction "2_2") (pintype "passive"))
    )
    (net (code "8") (name "IO2") (class "Default")
      (node (ref "IC3") (pin "14") (pinfunction "GPIO2_14") (pintype "bidirectional"))
      (node (ref "RUNLED") (pin "2") (pinfunction "2_2") (pintype "passive"))
    )
    (net (code "9") (name "IO4") (class "Default")
      (node (ref "I2C") (pin "1") (pinfunction "1_1") (pintype "passive"))
      (node (ref "IC3") (pin "16") (pinfunction "GPIO4_16") (pintype "bidirectional"))
      (node (ref "R8") (pin "2") (pinfunction "2_2") (pintype "passive"))
      (node (ref "U2") (pin "3") (pinfunction "SDA_3") (pintype "input"))
    )
    (net (code "10") (name "IO5") (class "Default")
      (node (ref "I2C") (pin "2") (pinfunction "2_2") (pintype "passive"))
      (node (ref "IC3") (pin "24") (pinfunction "GPIO5_24") (pintype "bidirectional"))
      (node (ref "R18") (pin "1") (pinfunction "1_1") (pintype "passive"))
      (node (ref "U2") (pin "2") (pinfunction "SCL_2") (pintype "input"))
    )
    (net (code "11") (name "IO6") (class "Default")
      (node (ref "IC3") (pin "21") (pinfunction "SD_CLK_21") (pintype "bidirectional"))
    )
    (net (code "12") (name "IO7") (class "Default")
      (node (ref "IC3") (pin "22") (pinfunction "SD_DATA_0_22") (pintype "bidirectional"))
    )
    (net (code "13") (name "IO8") (class "Default")
      (node (ref "IC3") (pin "23") (pinfunction "SD_DATA_1_23") (pintype "bidirectional"))
    )
    (net (code "14") (name "IO9") (class "Default")
      (node (ref "IC3") (pin "18") (pinfunction "SD_DATA_2_18") (pintype "bidirectional"))
    )
    (net (code "15") (name "IO10") (class "Default")
      (node (ref "IC3") (pin "19") (pinfunction "SD_DATA_3_19") (pintype "bidirectional"))
    )
    (net (code "16") (name "IO11") (class "Default")
      (node (ref "IC3") (pin "20") (pinfunction "SD_CMD_20") (pintype "bidirectional"))
    )
    (net (code "17") (name "IO12") (class "Default")
      (node (ref "IC3") (pin "10") (pinfunction "MTDI_10") (pintype "bidirectional"))
      (node (ref "SDCARD") (pin "2") (pinfunction "2_2") (pintype "passive"))
      (node (ref "TP6") (pin "TP") (pinfunction "TP_TP") (pintype "input"))
    )
    (net (code "18") (name "IO13") (class "Default")
      (node (ref "IC3") (pin "12") (pinfunction "MTCK_12") (pintype "bidirectional"))
      (node (ref "SDCARD") (pin "3") (pinfunction "3_3") (pintype "passive"))
      (node (ref "U3") (pin "20") (pinfunction "TXD1_20") (pintype "output"))
    )
    (net (code "19") (name "IO14") (class "Default")
      (node (ref "IC3") (pin "9") (pinfunction "MTMS_9") (pintype "bidirectional"))
      (node (ref "SDCARD") (pin "4") (pinfunction "4_4") (pintype "passive"))
    )
    (net (code "20") (name "IO15") (class "Default")
      (node (ref "IC3") (pin "13") (pinfunction "MTDO_13") (pintype "bidirectional"))
      (node (ref "R5") (pin "2") (pinfunction "2_2") (pintype "passive"))
      (node (ref "TP9") (pin "TP") (pinfunction "TP_TP") (pintype "input"))
      (node (ref "U3") (pin "21") (pinfunction "RXD1_21") (pintype "input"))
    )
    (net (code "21") (name "IO16") (class "Default")
      (node (ref "IC3") (pin "8") (pinfunction "XPD_DCDC_8") (pintype "bidirectional"))
      (node (ref "SDCARD") (pin "1") (pinfunction "1_1") (pintype "passive"))
    )
    (net (code "22") (name "N$17") (class "Default")
      (node (ref "C27") (pin "+") (pinfunction "+_+") (pintype "passive"))
      (node (ref "D11") (pin "C") (pinfunction "C_C") (pintype "passive"))
      (node (ref "U4") (pin "1") (pinfunction "VBAT_1") (pintype "power_in"))
      (node (ref "U4") (pin "42") (pinfunction "VBAT_42") (pintype "power_in"))
    )
    (net (code "23") (name "Net-(ANT1-1)") (class "Default")
      (node (ref "ANT1") (pin "ANT") (pinfunction "1_ANT") (pintype "bidirectional"))
      (node (ref "C5") (pin "1") (pinfunction "1_1") (pintype "passive"))
      (node (ref "L1") (pin "2") (pinfunction "2_2") (pintype "passive"))
    )
    (net (code "24") (name "Net-(BT2-Pad+)") (class "Default")
      (node (ref "BT2") (pin "+") (pinfunction "+_+") (pintype "power_in"))
      (node (ref "R28") (pin "1") (pinfunction "1_1") (pintype "passive"))
    )
    (net (code "25") (name "Net-(BUZB-S)") (class "Default")
      (node (ref "BUZ") (pin "2") (pinfunction "S_2") (pintype "passive"))
      (node (ref "Q1") (pin "D") (pinfunction "D_D") (pintype "passive"))
    )
    (net (code "26") (name "Net-(IC3-CHIP_EN)") (class "Default")
      (node (ref "C8") (pin "1") (pinfunction "1_1") (pintype "passive"))
      (node (ref "IC3") (pin "7") (pinfunction "CHIP_EN_7") (pintype "bidirectional"))
      (node (ref "R4") (pin "2") (pinfunction "2_2") (pintype "passive"))
    )
    (net (code "27") (name "Net-(IC3-EXT_RSTB)") (class "Default")
      (node (ref "IC3") (pin "32") (pinfunction "EXT_RSTB_32") (pintype "bidirectional"))
      (node (ref "R1") (pin "1") (pinfunction "1_1") (pintype "passive"))
    )
    (net (code "28") (name "Net-(IC3-LNA)") (class "Default")
      (node (ref "C4") (pin "1") (pinfunction "1_1") (pintype "passive"))
      (node (ref "IC3") (pin "2") (pinfunction "LNA_2") (pintype "bidirectional"))
      (node (ref "L1") (pin "1") (pinfunction "1_1") (pintype "passive"))
    )
    (net (code "29") (name "Net-(IC3-RES12K)") (class "Default")
      (node (ref "IC3") (pin "31") (pinfunction "RES12K_31") (pintype "bidirectional"))
      (node (ref "R3") (pin "2") (pinfunction "2_2") (pintype "passive"))
    )
    (net (code "30") (name "Net-(IC3-XTAL_IN)") (class "Default")
      (node (ref "C2") (pin "2") (pinfunction "2_2") (pintype "passive"))
      (node (ref "IC3") (pin "28") (pinfunction "XTAL_IN_28") (pintype "bidirectional"))
      (node (ref "Q2") (pin "1") (pinfunction "1_1") (pintype "passive"))
    )
    (net (code "31") (name "Net-(IC3-XTAL_OUT)") (class "Default")
      (node (ref "C3") (pin "2") (pinfunction "2_2") (pintype "passive"))
      (node (ref "IC3") (pin "27") (pinfunction "XTAL_OUT_27") (pintype "bidirectional"))
      (node (ref "Q2") (pin "3") (pinfunction "3_3") (pintype "passive"))
    )
    (net (code "32") (name "Net-(IC6-VI)") (class "Default")
      (node (ref "C21") (pin "+") (pinfunction "+_+") (pintype "passive"))
      (node (ref "D2") (pin "C") (pinfunction "C_C") (pintype "passive"))
      (node (ref "IC6") (pin "1") (pinfunction "VI_1") (pintype "input"))
    )
    (net (code "33") (name "Net-(J1-SIGNAL)") (class "Default")
      (node (ref "J1") (pin "FEED") (pinfunction "SIGNAL_FEED") (pintype "bidirectional"))
      (node (ref "L3") (pin "2") (pinfunction "2_2") (pintype "passive"))
      (node (ref "U3") (pin "11") (pinfunction "RF_IN_11") (pintype "input"))
    )
    (net (code "34") (name "Net-(J3-SIGNAL)") (class "Default")
      (node (ref "J3") (pin "FEED") (pinfunction "SIGNAL_FEED") (pintype "bidirectional"))
      (node (ref "U4") (pin "40") (pinfunction "ANT_40") (pintype "bidirectional"))
    )
    (net (code "35") (name "Net-(K6A-2)") (class "Default")
      (node (ref "D1") (pin "A") (pinfunction "A_A") (pintype "passive"))
      (node (ref "K6") (pin "16") (pinfunction "2_16") (pintype "passive"))
      (node (ref "T6") (pin "C") (pinfunction "C_C") (pintype "passive"))
    )
    (net (code "36") (name "Net-(K6C-S)") (class "Default")
      (node (ref "D16") (pin "A") (pinfunction "A_A") (pintype "passive"))
      (node (ref "D17") (pin "A") (pinfunction "A_A") (pintype "passive"))
      (node (ref "K6") (pin "S2") (pinfunction "S_S2") (pintype "passive"))
    )
    (net (code "37") (name "Net-(K7A-2)") (class "Default")
      (node (ref "D12") (pin "A") (pinfunction "A_A") (pintype "passive"))
      (node (ref "K7") (pin "16") (pinfunction "2_16") (pintype "passive"))
      (node (ref "T7") (pin "C") (pinfunction "C_C") (pintype "passive"))
    )
    (net (code "38") (name "Net-(K7B-P)") (class "Default")
      (node (ref "K7") (pin "P1") (pinfunction "P_P1") (pintype "passive"))
      (node (ref "SJ2") (pin "2") (pinfunction "2_2") (pintype "passive"))
    )
    (net (code "39") (name "Net-(K7B-S)") (class "Default")
      (node (ref "K7") (pin "S1") (pinfunction "S_S1") (pintype "passive"))
      (node (ref "X9") (pin "2") (pinfunction "S_2") (pintype "passive"))
    )
    (net (code "40") (name "Net-(K8A-2)") (class "Default")
      (node (ref "D13") (pin "A") (pinfunction "A_A") (pintype "passive"))
      (node (ref "K8") (pin "16") (pinfunction "2_16") (pintype "passive"))
      (node (ref "T8") (pin "C") (pinfunction "C_C") (pintype "passive"))
    )
    (net (code "41") (name "Net-(K8B-O)") (class "Default")
      (node (ref "K8") (pin "O1") (pinfunction "O_O1") (pintype "passive"))
      (node (ref "X10") (pin "2") (pinfunction "S_2") (pintype "passive"))
    )
    (net (code "42") (name "Net-(K8B-P)") (class "Default")
      (node (ref "K8") (pin "P1") (pinfunction "P_P1") (pintype "passive"))
      (node (ref "SJ3") (pin "2") (pinfunction "2_2") (pintype "passive"))
    )
    (net (code "43") (name "Net-(K8C-S)") (class "Default")
      (node (ref "K8") (pin "S2") (pinfunction "S_S2") (pintype "passive"))
      (node (ref "X10") (pin "1") (pinfunction "S_1") (pintype "passive"))
    )
    (net (code "44") (name "Net-(K9A-2)") (class "Default")
      (node (ref "D14") (pin "A") (pinfunction "A_A") (pintype "passive"))
      (node (ref "K9") (pin "16") (pinfunction "2_16") (pintype "passive"))
      (node (ref "T9") (pin "C") (pinfunction "C_C") (pintype "passive"))
    )
    (net (code "45") (name "Net-(K9B-O)") (class "Default")
      (node (ref "K9") (pin "O1") (pinfunction "O_O1") (pintype "passive"))
      (node (ref "X11") (pin "2") (pinfunction "S_2") (pintype "passive"))
    )
    (net (code "46") (name "Net-(K9B-P)") (class "Default")
      (node (ref "K9") (pin "P1") (pinfunction "P_P1") (pintype "passive"))
      (node (ref "SJ1") (pin "2") (pinfunction "2_2") (pintype "passive"))
    )
    (net (code "47") (name "Net-(K9C-S)") (class "Default")
      (node (ref "K9") (pin "S2") (pinfunction "S_S2") (pintype "passive"))
      (node (ref "X11") (pin "1") (pinfunction "S_1") (pintype "passive"))
    )
    (net (code "48") (name "Net-(K10A-2)") (class "Default")
      (node (ref "D15") (pin "A") (pinfunction "A_A") (pintype "passive"))
      (node (ref "K10") (pin "16") (pinfunction "2_16") (pintype "passive"))
      (node (ref "T10") (pin "C") (pinfunction "C_C") (pintype "passive"))
    )
    (net (code "49") (name "Net-(K10B-O)") (class "Default")
      (node (ref "K10") (pin "O1") (pinfunction "O_O1") (pintype "passive"))
      (node (ref "X12") (pin "2") (pinfunction "S_2") (pintype "passive"))
    )
    (net (code "50") (name "Net-(K10C-S)") (class "Default")
      (node (ref "K10") (pin "S2") (pinfunction "S_S2") (pintype "passive"))
      (node (ref "X12") (pin "1") (pinfunction "S_1") (pintype "passive"))
    )
    (net (code "51") (name "Net-(L3-Pad1)") (class "Default")
      (node (ref "L3") (pin "1") (pinfunction "1_1") (pintype "passive"))
      (node (ref "R9") (pin "2") (pinfunction "2_2") (pintype "passive"))
    )
    (net (code "52") (name "Net-(LED2-PadA)") (class "Default")
      (node (ref "LED2") (pin "A") (pinfunction "A_A") (pintype "passive"))
      (node (ref "R27") (pin "2") (pinfunction "2_2") (pintype "passive"))
    )
    (net (code "53") (name "Net-(LED3-PadA)") (class "Default")
      (node (ref "LED3") (pin "A") (pinfunction "A_A") (pintype "passive"))
      (node (ref "R23") (pin "2") (pinfunction "2_2") (pintype "passive"))
    )
    (net (code "54") (name "Net-(Q1-PadG)") (class "Default")
      (node (ref "Q1") (pin "G") (pinfunction "G_G") (pintype "passive"))
      (node (ref "R10") (pin "2") (pinfunction "2_2") (pintype "passive"))
    )
    (net (code "55") (name "Net-(R22-Pad2)") (class "Default")
      (node (ref "R22") (pin "2") (pinfunction "2_2") (pintype "passive"))
      (node (ref "R24") (pin "2") (pinfunction "2_2") (pintype "passive"))
      (node (ref "T6") (pin "B") (pinfunction "B_B") (pintype "passive"))
    )
    (net (code "56") (name "Net-(R25-Pad2)") (class "Default")
      (node (ref "R25") (pin "2") (pinfunction "2_2") (pintype "passive"))
      (node (ref "R26") (pin "2") (pinfunction "2_2") (pintype "passive"))
      (node (ref "T7") (pin "B") (pinfunction "B_B") (pintype "passive"))
    )
    (net (code "57") (name "Net-(R30-Pad2)") (class "Default")
      (node (ref "R30") (pin "2") (pinfunction "2_2") (pintype "passive"))
      (node (ref "R31") (pin "2") (pinfunction "2_2") (pintype "passive"))
      (node (ref "T8") (pin "B") (pinfunction "B_B") (pintype "passive"))
    )
    (net (code "58") (name "Net-(R32-Pad2)") (class "Default")
      (node (ref "R32") (pin "2") (pinfunction "2_2") (pintype "passive"))
      (node (ref "R33") (pin "2") (pinfunction "2_2") (pintype "passive"))
      (node (ref "T9") (pin "B") (pinfunction "B_B") (pintype "passive"))
    )
    (net (code "59") (name "Net-(R34-Pad2)") (class "Default")
      (node (ref "R34") (pin "2") (pinfunction "2_2") (pintype "passive"))
      (node (ref "R35") (pin "2") (pinfunction "2_2") (pintype "passive"))
      (node (ref "T10") (pin "B") (pinfunction "B_B") (pintype "passive"))
    )
    (net (code "60") (name "Net-(U2-ELE0)") (class "Default")
      (node (ref "TP10") (pin "TP") (pinfunction "TP_TP") (pintype "input"))
      (node (ref "U2") (pin "8") (pinfunction "ELE0_8") (pintype "output"))
    )
    (net (code "61") (name "Net-(U2-ELE1)") (class "Default")
      (node (ref "TP8") (pin "TP") (pinfunction "TP_TP") (pintype "input"))
      (node (ref "U2") (pin "9") (pinfunction "ELE1_9") (pintype "output"))
    )
    (net (code "62") (name "Net-(U2-ELE2)") (class "Default")
      (node (ref "TP5") (pin "TP") (pinfunction "TP_TP") (pintype "input"))
      (node (ref "U2") (pin "10") (pinfunction "ELE2_10") (pintype "output"))
    )
    (net (code "63") (name "Net-(U2-ELE3)") (class "Default")
      (node (ref "TP7") (pin "TP") (pinfunction "TP_TP") (pintype "input"))
      (node (ref "U2") (pin "11") (pinfunction "ELE3_11") (pintype "output"))
    )
    (net (code "64") (name "Net-(U2-ELE4)") (class "Default")
      (node (ref "TP11") (pin "TP") (pinfunction "TP_TP") (pintype "input"))
      (node (ref "U2") (pin "12") (pinfunction "ELE4_12") (pintype "output"))
    )
    (net (code "65") (name "Net-(U2-REXT)") (class "Default")
      (node (ref "R29") (pin "2") (pinfunction "2_2") (pintype "passive"))
      (node (ref "U2") (pin "7") (pinfunction "REXT_7") (pintype "input"))
    )
    (net (code "66") (name "Net-(U2-VREG)") (class "Default")
      (node (ref "C17") (pin "1") (pinfunction "1_1") (pintype "passive"))
      (node (ref "U2") (pin "5") (pinfunction "VREG_5") (pintype "input"))
    )
    (net (code "67") (name "Net-(U2-~{IRQ})") (class "Default")
      (node (ref "R19") (pin "1") (pinfunction "1_1") (pintype "passive"))
      (node (ref "U2") (pin "1") (pinfunction "~{IRQ}_1") (pintype "input"))
    )
    (net (code "68") (name "Net-(U3-RSVD_8)") (class "Default")
      (node (ref "R9") (pin "1") (pinfunction "1_1") (pintype "passive"))
      (node (ref "U3") (pin "8") (pinfunction "RSVD_8_8") (pintype "passive"))
      (node (ref "U3") (pin "9") (pinfunction "VCC_RF_9") (pintype "output"))
    )
    (net (code "69") (name "Net-(U3-TIMEPULSE)") (class "Default")
      (node (ref "R27") (pin "1") (pinfunction "1_1") (pintype "passive"))
      (node (ref "U3") (pin "3") (pinfunction "TIMEPULSE_3") (pintype "output"))
    )
    (net (code "70") (name "Net-(U3-V_BCKP)") (class "Default")
      (node (ref "D10") (pin "C") (pinfunction "C_C") (pintype "passive"))
      (node (ref "R28") (pin "2") (pinfunction "2_2") (pintype "passive"))
      (node (ref "U3") (pin "22") (pinfunction "V_BCKP_22") (pintype "power_in"))
    )
    (net (code "71") (name "Net-(U4-NETLIGHT)") (class "Default")
      (node (ref "R23") (pin "1") (pinfunction "1_1") (pintype "passive"))
      (node (ref "U4") (pin "64") (pinfunction "NETLIGHT_64") (pintype "output"))
    )
    (net (code "72") (name "Net-(X8A-S)") (class "Default")
      (node (ref "D17") (pin "C") (pinfunction "C_C") (pintype "passive"))
      (node (ref "X8") (pin "1") (pinfunction "S_1") (pintype "passive"))
    )
    (net (code "73") (name "Net-(X8B-S)") (class "Default")
      (node (ref "D16") (pin "C") (pinfunction "C_C") (pintype "passive"))
      (node (ref "X8") (pin "2") (pinfunction "S_2") (pintype "passive"))
    )
    (net (code "74") (name "REL1") (class "Default")
      (node (ref "R22") (pin "1") (pinfunction "1_1") (pintype "passive"))
      (node (ref "U2") (pin "16") (pinfunction "ELE8_16") (pintype "output"))
    )
    (net (code "75") (name "REL2") (class "Default")
      (node (ref "R25") (pin "1") (pinfunction "1_1") (pintype "passive"))
      (node (ref "U2") (pin "17") (pinfunction "ELE9_17") (pintype "output"))
    )
    (net (code "76") (name "REL3") (class "Default")
      (node (ref "R30") (pin "1") (pinfunction "1_1") (pintype "passive"))
      (node (ref "U2") (pin "18") (pinfunction "ELE10_18") (pintype "output"))
    )
    (net (code "77") (name "REL4") (class "Default")
      (node (ref "R32") (pin "1") (pinfunction "1_1") (pintype "passive"))
      (node (ref "U2") (pin "19") (pinfunction "ELE11_19") (pintype "output"))
    )
    (net (code "78") (name "REL5") (class "Default")
      (node (ref "R34") (pin "1") (pinfunction "1_1") (pintype "passive"))
      (node (ref "U2") (pin "14") (pinfunction "ELE6_14") (pintype "output"))
    )
    (net (code "79") (name "RST") (class "Default")
      (node (ref "RST1") (pin "TP") (pinfunction "TP_TP") (pintype "input"))
    )
    (net (code "80") (name "RXD") (class "Default")
      (node (ref "IC3") (pin "25") (pinfunction "U0RXD_25") (pintype "bidirectional"))
      (node (ref "RX2") (pin "TP") (pinfunction "TP_TP") (pintype "input"))
      (node (ref "TP3") (pin "TP") (pinfunction "TP_TP") (pintype "input"))
      (node (ref "U4") (pin "32") (pinfunction "TXD_32") (pintype "output"))
    )
    (net (code "81") (name "RXD1") (class "Default")
      (node (ref "RX3") (pin "TP") (pinfunction "TP_TP") (pintype "input"))
    )
    (net (code "82") (name "SCL2") (class "Default")
      (node (ref "IC4") (pin "6") (pinfunction "SCL_6") (pintype "input"))
      (node (ref "U3") (pin "19") (pinfunction "SCL2_19") (pintype "bidirectional"))
    )
    (net (code "83") (name "SDA2") (class "Default")
      (node (ref "IC4") (pin "5") (pinfunction "SDA_5") (pintype "bidirectional"))
      (node (ref "U3") (pin "18") (pinfunction "SDA2_18") (pintype "bidirectional"))
    )
    (net (code "84") (name "SIMCLK") (class "Default")
      (node (ref "J4") (pin "C3") (pinfunction "CLK_C3") (pintype "input"))
      (node (ref "U4") (pin "55") (pinfunction "SIM_CLK_55") (pintype "output"))
    )
    (net (code "85") (name "SIMDATA") (class "Default")
      (node (ref "C29") (pin "2") (pinfunction "2_2") (pintype "passive"))
      (node (ref "J4") (pin "C7") (pinfunction "I/O_C7") (pintype "bidirectional"))
      (node (ref "U4") (pin "14") (pinfunction "SIM_DATA_14") (pintype "bidirectional"))
    )
    (net (code "86") (name "SIMRST") (class "Default")
      (node (ref "J4") (pin "C2") (pinfunction "RST_C2") (pintype "input"))
      (node (ref "U4") (pin "15") (pinfunction "SIM_RST_15") (pintype "output"))
    )
    (net (code "87") (name "SIMVCC") (class "Default")
      (node (ref "C28") (pin "1") (pinfunction "1_1") (pintype "passive"))
      (node (ref "J4") (pin "C1") (pinfunction "VCC_C1") (pintype "power_in"))
      (node (ref "U4") (pin "16") (pinfunction "VSIM_16") (pintype "output"))
    )
    (net (code "88") (name "TXD") (class "Default")
      (node (ref "IC3") (pin "26") (pinfunction "U0TXD_26") (pintype "bidirectional"))
      (node (ref "TP2") (pin "TP") (pinfunction "TP_TP") (pintype "input"))
      (node (ref "TX2") (pin "TP") (pinfunction "TP_TP") (pintype "input"))
      (node (ref "U4") (pin "31") (pinfunction "RXD_31") (pintype "input"))
    )
    (net (code "89") (name "TXD1") (class "Default")
      (node (ref "TX3") (pin "TP") (pinfunction "TP_TP") (pintype "input"))
    )
    (net (code "90") (name "VCC_2") (class "Default")
      (node (ref "V+3") (pin "TP") (pinfunction "TP_TP") (pintype "input"))
    )
    (net (code "91") (name "VEXT") (class "Default")
      (node (ref "U4") (pin "18") (pinfunction "VEXT_18") (pintype "power_in"))
    )
    (net (code "92") (name "VIBRATION") (class "Default")
      (node (ref "R11") (pin "1") (pinfunction "1_1") (pintype "passive"))
      (node (ref "S3") (pin "2") (pinfunction "2_2") (pintype "passive"))
      (node (ref "U2") (pin "13") (pinfunction "ELE5_13") (pintype "output"))
    )
    (net (code "93") (name "VPP") (class "Default")
      (node (ref "J4") (pin "C6") (pinfunction "VPP_C6") (pintype "power_in"))
    )
    (net (code "94") (name "VRTC") (class "Default")
      (node (ref "U4") (pin "56") (pinfunction "VRTC_56") (pintype "power_in"))
    )
    (net (code "95") (name "unconnected-(IC3-TOUT-Pad6)") (class "Default")
      (node (ref "IC3") (pin "6") (pinfunction "TOUT_6") (pintype "bidirectional"))
    )
    (net (code "96") (name "unconnected-(IC3-VDD_RTC-Pad5)") (class "Default")
      (node (ref "IC3") (pin "5") (pinfunction "VDD_RTC_5") (pintype "bidirectional"))
    )
    (net (code "97") (name "unconnected-(IC8-NC{slash}FB-Pad4)") (class "Default")
      (node (ref "IC8") (pin "4") (pinfunction "NC/FB_4") (pintype "passive"))
    )
    (net (code "98") (name "unconnected-(K6B-O-PadO1)") (class "Default")
      (node (ref "K6") (pin "O1") (pinfunction "O_O1") (pintype "passive"))
    )
    (net (code "99") (name "unconnected-(K6B-P-PadP1)") (class "Default")
      (node (ref "K6") (pin "P1") (pinfunction "P_P1") (pintype "passive"))
    )
    (net (code "100") (name "unconnected-(K6B-S-PadS1)") (class "Default")
      (node (ref "K6") (pin "S1") (pinfunction "S_S1") (pintype "passive"))
    )
    (net (code "101") (name "unconnected-(K6C-O-PadO2)") (class "Default")
      (node (ref "K6") (pin "O2") (pinfunction "O_O2") (pintype "passive"))
    )
    (net (code "102") (name "unconnected-(K7B-O-PadO1)") (class "Default")
      (node (ref "K7") (pin "O1") (pinfunction "O_O1") (pintype "passive"))
    )
    (net (code "103") (name "unconnected-(K7C-O-PadO2)") (class "Default")
      (node (ref "K7") (pin "O2") (pinfunction "O_O2") (pintype "passive"))
    )
    (net (code "104") (name "unconnected-(K7C-S-PadS2)") (class "Default")
      (node (ref "K7") (pin "S2") (pinfunction "S_S2") (pintype "passive"))
    )
    (net (code "105") (name "unconnected-(K8B-S-PadS1)") (class "Default")
      (node (ref "K8") (pin "S1") (pinfunction "S_S1") (pintype "passive"))
    )
    (net (code "106") (name "unconnected-(K8C-O-PadO2)") (class "Default")
      (node (ref "K8") (pin "O2") (pinfunction "O_O2") (pintype "passive"))
    )
    (net (code "107") (name "unconnected-(K9B-S-PadS1)") (class "Default")
      (node (ref "K9") (pin "S1") (pinfunction "S_S1") (pintype "passive"))
    )
    (net (code "108") (name "unconnected-(K9C-O-PadO2)") (class "Default")
      (node (ref "K9") (pin "O2") (pinfunction "O_O2") (pintype "passive"))
    )
    (net (code "109") (name "unconnected-(K10B-P-PadP1)") (class "Default")
      (node (ref "K10") (pin "P1") (pinfunction "P_P1") (pintype "passive"))
    )
    (net (code "110") (name "unconnected-(K10B-S-PadS1)") (class "Default")
      (node (ref "K10") (pin "S1") (pinfunction "S_S1") (pintype "passive"))
    )
    (net (code "111") (name "unconnected-(K10C-O-PadO2)") (class "Default")
      (node (ref "K10") (pin "O2") (pinfunction "O_O2") (pintype "passive"))
    )
    (net (code "112") (name "unconnected-(U2-ADDR-Pad4)") (class "Default")
      (node (ref "U2") (pin "4") (pinfunction "ADDR_4") (pintype "input"))
    )
    (net (code "113") (name "unconnected-(U3-CFG_GPS0{slash}SCK-Pad16)") (class "Default")
      (node (ref "U3") (pin "16") (pinfunction "CFG_GPS0/SCK_16") (pintype "input"))
    )
    (net (code "114") (name "unconnected-(U3-EXTINT0-Pad4)") (class "Default")
      (node (ref "U3") (pin "4") (pinfunction "EXTINT0_4") (pintype "input"))
    )
    (net (code "115") (name "unconnected-(U3-MISO{slash}CFG_COM1-Pad15)") (class "Default")
      (node (ref "U3") (pin "15") (pinfunction "MISO/CFG_COM1_15") (pintype "input"))
    )
    (net (code "116") (name "unconnected-(U3-MOSI{slash}CFG_COM0-Pad14)") (class "Default")
      (node (ref "U3") (pin "14") (pinfunction "MOSI/CFG_COM0_14") (pintype "bidirectional"))
    )
    (net (code "117") (name "unconnected-(U3-RSVD_17-Pad17)") (class "Default")
      (node (ref "U3") (pin "17") (pinfunction "RSVD_17_17") (pintype "passive"))
    )
    (net (code "118") (name "unconnected-(U3-SS_N-Pad2)") (class "Default")
      (node (ref "U3") (pin "2") (pinfunction "SS_N_2") (pintype "input"))
    )
    (net (code "119") (name "unconnected-(U3-USB_DM-Pad5)") (class "Default")
      (node (ref "U3") (pin "5") (pinfunction "USB_DM_5") (pintype "bidirectional"))
    )
    (net (code "120") (name "unconnected-(U3-USB_DP-Pad6)") (class "Default")
      (node (ref "U3") (pin "6") (pinfunction "USB_DP_6") (pintype "bidirectional"))
    )
    (net (code "121") (name "unconnected-(U4-ADC-Pad50)") (class "Default")
      (node (ref "U4") (pin "50") (pinfunction "ADC_50") (pintype "input"))
    )
    (net (code "122") (name "unconnected-(U4-BPI_BUSI-Pad5)") (class "Default")
      (node (ref "U4") (pin "5") (pinfunction "BPI_BUSI_5") (pintype "output"))
    )
    (net (code "123") (name "unconnected-(U4-COL0-Pad20)") (class "Default")
      (node (ref "U4") (pin "20") (pinfunction "COL0_20") (pintype "input"))
    )
    (net (code "124") (name "unconnected-(U4-COL1-Pad25)") (class "Default")
      (node (ref "U4") (pin "25") (pinfunction "COL1_25") (pintype "input"))
    )
    (net (code "125") (name "unconnected-(U4-COL2-Pad22)") (class "Default")
      (node (ref "U4") (pin "22") (pinfunction "COL2_22") (pintype "input"))
    )
    (net (code "126") (name "unconnected-(U4-COL3-Pad21)") (class "Default")
      (node (ref "U4") (pin "21") (pinfunction "COL3_21") (pintype "input"))
    )
    (net (code "127") (name "unconnected-(U4-COL4-Pad24)") (class "Default")
      (node (ref "U4") (pin "24") (pinfunction "COL4_24") (pintype "input"))
    )
    (net (code "128") (name "unconnected-(U4-CTS-Pad34)") (class "Default")
      (node (ref "U4") (pin "34") (pinfunction "CTS_34") (pintype "output"))
    )
    (net (code "129") (name "unconnected-(U4-FM_ANT_N-Pad57)") (class "Default")
      (node (ref "U4") (pin "57") (pinfunction "FM_ANT_N_57") (pintype "input"))
    )
    (net (code "130") (name "unconnected-(U4-FM_ANT_P-Pad17)") (class "Default")
      (node (ref "U4") (pin "17") (pinfunction "FM_ANT_P_17") (pintype "input"))
    )
    (net (code "131") (name "unconnected-(U4-GPIO1-Pad3)") (class "Default")
      (node (ref "U4") (pin "3") (pinfunction "GPIO1_3") (pintype "bidirectional"))
    )
    (net (code "132") (name "unconnected-(U4-GPIO2-Pad27)") (class "Default")
      (node (ref "U4") (pin "27") (pinfunction "GPIO2_27") (pintype "bidirectional"))
    )
    (net (code "133") (name "unconnected-(U4-GPIO3-Pad28)") (class "Default")
      (node (ref "U4") (pin "28") (pinfunction "GPIO3_28") (pintype "bidirectional"))
    )
    (net (code "134") (name "unconnected-(U4-ISINK0-Pad47)") (class "Default")
      (node (ref "U4") (pin "47") (pinfunction "ISINK0_47") (pintype "input"))
    )
    (net (code "135") (name "unconnected-(U4-ISINK1-Pad46)") (class "Default")
      (node (ref "U4") (pin "46") (pinfunction "ISINK1_46") (pintype "input"))
    )
    (net (code "136") (name "unconnected-(U4-MIC1N-Pad12)") (class "Default")
      (node (ref "U4") (pin "12") (pinfunction "MIC1N_12") (pintype "input"))
    )
    (net (code "137") (name "unconnected-(U4-MIC1P-Pad52)") (class "Default")
      (node (ref "U4") (pin "52") (pinfunction "MIC1P_52") (pintype "input"))
    )
    (net (code "138") (name "unconnected-(U4-MIC2N-Pad10)") (class "Default")
      (node (ref "U4") (pin "10") (pinfunction "MIC2N_10") (pintype "input"))
    )
    (net (code "139") (name "unconnected-(U4-MIC2P-Pad9)") (class "Default")
      (node (ref "U4") (pin "9") (pinfunction "MIC2P_9") (pintype "input"))
    )
    (net (code "140") (name "unconnected-(U4-PCMCLK-Pad29)") (class "Default")
      (node (ref "U4") (pin "29") (pinfunction "PCMCLK_29") (pintype "output"))
    )
    (net (code "141") (name "unconnected-(U4-PCMIN-Pad66)") (class "Default")
      (node (ref "U4") (pin "66") (pinfunction "PCMIN_66") (pintype "input"))
    )
    (net (code "142") (name "unconnected-(U4-PCMOUT-Pad30)") (class "Default")
      (node (ref "U4") (pin "30") (pinfunction "PCMOUT_30") (pintype "output"))
    )
    (net (code "143") (name "unconnected-(U4-PCMSYNC-Pad65)") (class "Default")
      (node (ref "U4") (pin "65") (pinfunction "PCMSYNC_65") (pintype "output"))
    )
    (net (code "144") (name "unconnected-(U4-PWM-Pad26)") (class "Default")
      (node (ref "U4") (pin "26") (pinfunction "PWM_26") (pintype "output"))
    )
    (net (code "145") (name "unconnected-(U4-PWRKEY-Pad48)") (class "Default")
      (node (ref "U4") (pin "48") (pinfunction "PWRKEY_48") (pintype "input"))
    )
    (net (code "146") (name "unconnected-(U4-RESET-Pad49)") (class "Default")
      (node (ref "U4") (pin "49") (pinfunction "RESET_49") (pintype "input"))
    )
    (net (code "147") (name "unconnected-(U4-ROW0-Pad62)") (class "Default")
      (node (ref "U4") (pin "62") (pinfunction "ROW0_62") (pintype "output"))
    )
    (net (code "148") (name "unconnected-(U4-ROW1-Pad60)") (class "Default")
      (node (ref "U4") (pin "60") (pinfunction "ROW1_60") (pintype "output"))
    )
    (net (code "149") (name "unconnected-(U4-ROW2-Pad61)") (class "Default")
      (node (ref "U4") (pin "61") (pinfunction "ROW2_61") (pintype "output"))
    )
    (net (code "150") (name "unconnected-(U4-ROW3-Pad23)") (class "Default")
      (node (ref "U4") (pin "23") (pinfunction "ROW3_23") (pintype "output"))
    )
    (net (code "151") (name "unconnected-(U4-ROW4-Pad63)") (class "Default")
      (node (ref "U4") (pin "63") (pinfunction "ROW4_63") (pintype "output"))
    )
    (net (code "152") (name "unconnected-(U4-RTS-Pad33)") (class "Default")
      (node (ref "U4") (pin "33") (pinfunction "RTS_33") (pintype "input"))
    )
    (net (code "153") (name "unconnected-(U4-SCL-Pad74)") (class "Default")
      (node (ref "U4") (pin "74") (pinfunction "SCL_74") (pintype "output"))
    )
    (net (code "154") (name "unconnected-(U4-SDA-Pad75)") (class "Default")
      (node (ref "U4") (pin "75") (pinfunction "SDA_75") (pintype "bidirectional"))
    )
    (net (code "155") (name "unconnected-(U4-SIMPRE-Pad54)") (class "Default")
      (node (ref "U4") (pin "54") (pinfunction "SIMPRE_54") (pintype "output"))
    )
    (net (code "156") (name "unconnected-(U4-SPK1N-Pad13)") (class "Default")
      (node (ref "U4") (pin "13") (pinfunction "SPK1N_13") (pintype "output"))
    )
    (net (code "157") (name "unconnected-(U4-SPK1P-Pad53)") (class "Default")
      (node (ref "U4") (pin "53") (pinfunction "SPK1P_53") (pintype "output"))
    )
    (net (code "158") (name "unconnected-(U4-SPK2N-Pad11)") (class "Default")
      (node (ref "U4") (pin "11") (pinfunction "SPK2N_11") (pintype "output"))
    )
    (net (code "159") (name "unconnected-(U4-SPK2P-Pad51)") (class "Default")
      (node (ref "U4") (pin "51") (pinfunction "SPK2P_51") (pintype "output"))
    )
    (net (code "160") (name "unconnected-(U4-STATUS-Pad4)") (class "Default")
      (node (ref "U4") (pin "4") (pinfunction "STATUS_4") (pintype "output"))
    )
    (net (code "161") (name "unconnected-(U4-UART_DCD-Pad70)") (class "Default")
      (node (ref "U4") (pin "70") (pinfunction "UART_DCD_70") (pintype "output"))
    )
    (net (code "162") (name "unconnected-(U4-UART_DTR-Pad69)") (class "Default")
      (node (ref "U4") (pin "69") (pinfunction "UART_DTR_69") (pintype "output"))
    )
    (net (code "163") (name "unconnected-(U4-UART_RI-Pad68)") (class "Default")
      (node (ref "U4") (pin "68") (pinfunction "UART_RI_68") (pintype "output"))
    )
    (net (code "164") (name "unconnected-(U4-USB_DM-Pad19)") (class "Default")
      (node (ref "U4") (pin "19") (pinfunction "USB_DM_19") (pintype "bidirectional"))
    )
    (net (code "165") (name "unconnected-(U4-USB_DP-Pad59)") (class "Default")
      (node (ref "U4") (pin "59") (pinfunction "USB_DP_59") (pintype "bidirectional"))
    )
    (net (code "166") (name "unconnected-(U4-VBUS-Pad7)") (class "Default")
      (node (ref "U4") (pin "7") (pinfunction "VBUS_7") (pintype "input"))
    )
    (net (code "167") (name "unconnected-(X9A-S-Pad1)") (class "Default")
      (node (ref "X9") (pin "1") (pinfunction "S_1") (pintype "passive"))
    )
  )
)
